# F103ZET6.net
KiCad netlist of a schematic drawn in Altium Designer
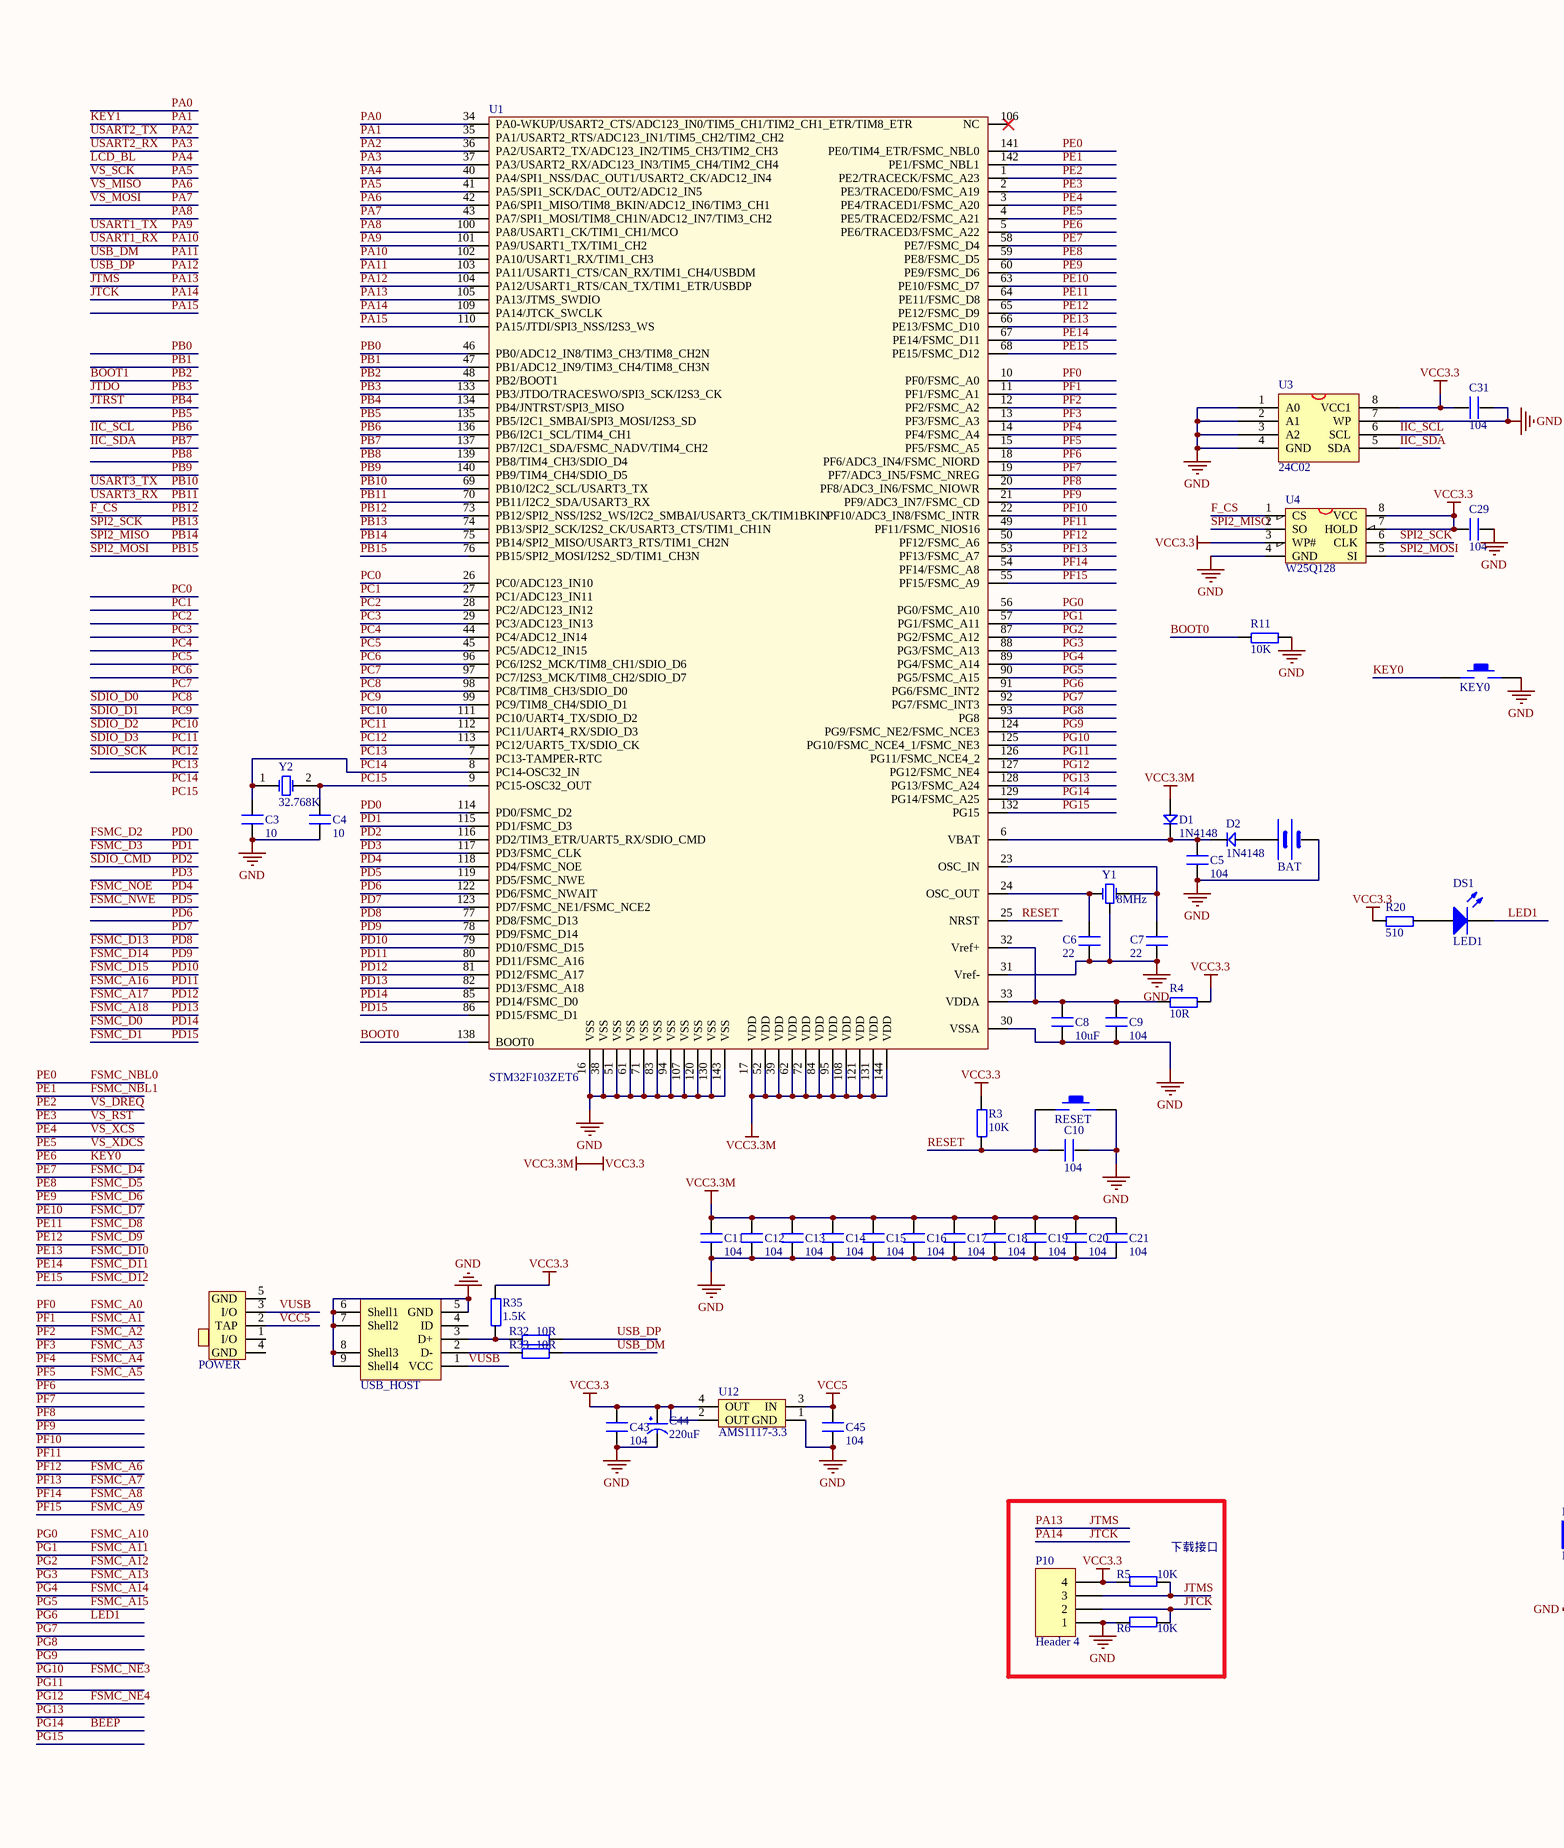
[diagram p0: F103ZET6.SchDoc, left]
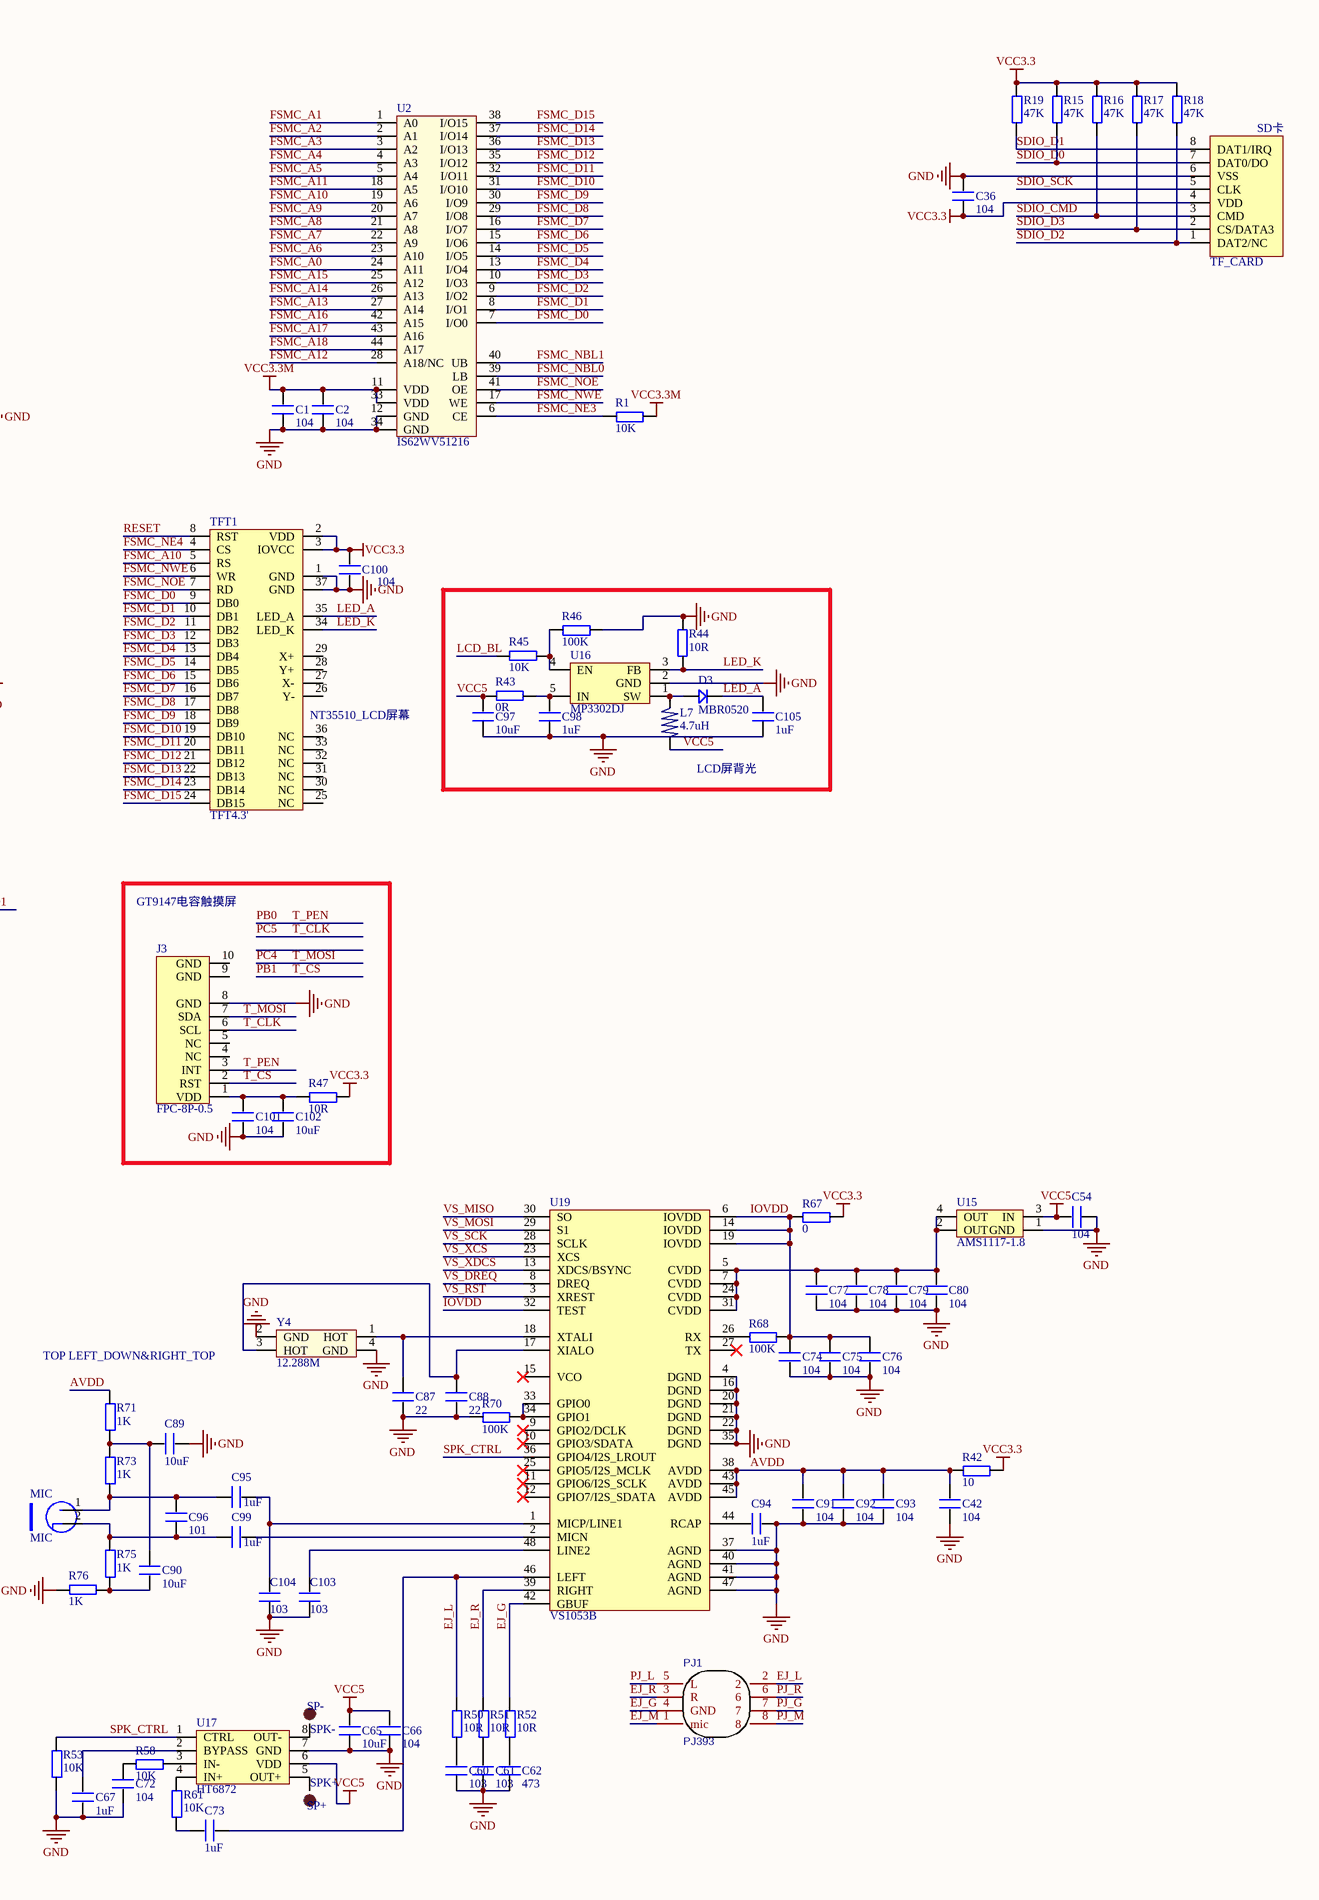
[diagram p1: F103ZET6.SchDoc, right]

(export (version "E")
  (design (tool "Eeschema 10.0.6"))
  (components
    (comp (ref "BAT")
      (value "BATT")
      (footprint "CR1220_A")
      (libsource (lib "WarShip V3 STM32103封装库") (part "BAT"))
    )
    (comp (ref "C1")
      (value "104")
      (footprint "C 0603_M")
      (libsource (lib "WarShip V3 STM32103封装库") (part "C"))
    )
    (comp (ref "C2")
      (value "104")
      (footprint "C 0603_M")
      (libsource (lib "WarShip V3 STM32103封装库") (part "C"))
    )
    (comp (ref "C3")
      (value "10")
      (footprint "C 0603_M")
      (libsource (lib "WarShip V3 STM32103封装库") (part "C"))
    )
    (comp (ref "C4")
      (value "10")
      (footprint "C 0603_M")
      (libsource (lib "WarShip V3 STM32103封装库") (part "C"))
    )
    (comp (ref "C5")
      (value "104")
      (footprint "C 0603_M")
      (libsource (lib "WarShip V3 STM32103封装库") (part "C"))
    )
    (comp (ref "C6")
      (value "22")
      (footprint "C 0603_M")
      (libsource (lib "WarShip V3 STM32103封装库") (part "C"))
    )
    (comp (ref "C7")
      (value "22")
      (footprint "C 0603_M")
      (libsource (lib "WarShip V3 STM32103封装库") (part "C"))
    )
    (comp (ref "C8")
      (value "10uF")
      (footprint "C 0805_M")
      (libsource (lib "WarShip V3 STM32103封装库") (part "C"))
    )
    (comp (ref "C9")
      (value "104")
      (footprint "C 0603_M")
      (libsource (lib "WarShip V3 STM32103封装库") (part "C"))
    )
    (comp (ref "C10")
      (value "104")
      (footprint "C 0603_M")
      (libsource (lib "WarShip V3 STM32103封装库") (part "C"))
    )
    (comp (ref "C11")
      (value "104")
      (footprint "C 0603_M")
      (libsource (lib "WarShip V3 STM32103封装库") (part "C"))
    )
    (comp (ref "C12")
      (value "104")
      (footprint "C 0603_M")
      (libsource (lib "WarShip V3 STM32103封装库") (part "C"))
    )
    (comp (ref "C13")
      (value "104")
      (footprint "C 0603_M")
      (libsource (lib "WarShip V3 STM32103封装库") (part "C"))
    )
    (comp (ref "C14")
      (value "104")
      (footprint "C 0603_M")
      (libsource (lib "WarShip V3 STM32103封装库") (part "C"))
    )
    (comp (ref "C15")
      (value "104")
      (footprint "C 0603_M")
      (libsource (lib "WarShip V3 STM32103封装库") (part "C"))
    )
    (comp (ref "C16")
      (value "104")
      (footprint "C 0603_M")
      (libsource (lib "WarShip V3 STM32103封装库") (part "C"))
    )
    (comp (ref "C17")
      (value "104")
      (footprint "C 0603_M")
      (libsource (lib "WarShip V3 STM32103封装库") (part "C"))
    )
    (comp (ref "C18")
      (value "104")
      (footprint "C 0603_M")
      (libsource (lib "WarShip V3 STM32103封装库") (part "C"))
    )
    (comp (ref "C19")
      (value "104")
      (footprint "C 0603_M")
      (libsource (lib "WarShip V3 STM32103封装库") (part "C"))
    )
    (comp (ref "C20")
      (value "104")
      (footprint "C 0603_M")
      (libsource (lib "WarShip V3 STM32103封装库") (part "C"))
    )
    (comp (ref "C21")
      (value "104")
      (footprint "C 0603_M")
      (libsource (lib "WarShip V3 STM32103封装库") (part "C"))
    )
    (comp (ref "C29")
      (value "104")
      (footprint "C 0603_M")
      (libsource (lib "WarShip V3 STM32103封装库") (part "C"))
    )
    (comp (ref "C31")
      (value "104")
      (footprint "C 0603_M")
      (libsource (lib "WarShip V3 STM32103封装库") (part "C"))
    )
    (comp (ref "C36")
      (value "104")
      (footprint "C 0603_M")
      (libsource (lib "WarShip V3 STM32103封装库") (part "C"))
    )
    (comp (ref "C42") (value "104") (footprint "C 0603_M") (libsource (lib "ATK-VS1053 MP3") (part "C")))
    (comp (ref "C43")
      (value "104")
      (footprint "C 0603_M")
      (libsource (lib "WarShip V3 STM32103封装库") (part "C"))
    )
    (comp (ref "C44")
      (value "220uF")
      (footprint "CT 6*6 - C")
      (libsource (lib "WarShip V3 STM32103封装库") (part "CAP"))
    )
    (comp (ref "C45")
      (value "104")
      (footprint "C 0603_M")
      (libsource (lib "WarShip V3 STM32103封装库") (part "C"))
    )
    (comp (ref "C54") (value "104") (footprint "C 0603_M") (libsource (lib "ATK-VS1053 MP3") (part "C")))
    (comp (ref "C60")
      (value "103")
      (footprint "C 0603_M")
      (libsource (lib "WarShip V3 STM32103封装库") (part "C"))
    )
    (comp (ref "C61")
      (value "103")
      (footprint "C 0603_M")
      (libsource (lib "WarShip V3 STM32103封装库") (part "C"))
    )
    (comp (ref "C62")
      (value "473")
      (footprint "C 0603_M")
      (libsource (lib "WarShip V3 STM32103封装库") (part "C"))
    )
    (comp (ref "C65")
      (value "10uF")
      (footprint "C 0805_M")
      (libsource (lib "WarShip V3 STM32103封装库") (part "C"))
    )
    (comp (ref "C66")
      (value "104")
      (footprint "C 0603_M")
      (libsource (lib "WarShip V3 STM32103封装库") (part "C"))
    )
    (comp (ref "C67")
      (value "1uF")
      (footprint "C 0603_M")
      (libsource (lib "WarShip V3 STM32103封装库") (part "C"))
    )
    (comp (ref "C72")
      (value "104")
      (footprint "C 0603_M")
      (libsource (lib "WarShip V3 STM32103封装库") (part "C"))
    )
    (comp (ref "C73")
      (value "1uF")
      (footprint "C 0603_M")
      (libsource (lib "WarShip V3 STM32103封装库") (part "C"))
    )
    (comp (ref "C74") (value "104") (footprint "C 0603_M") (libsource (lib "ATK-VS1053 MP3") (part "C")))
    (comp (ref "C75") (value "104") (footprint "C 0603_M") (libsource (lib "ATK-VS1053 MP3") (part "C")))
    (comp (ref "C76") (value "104") (footprint "C 0603_M") (libsource (lib "ATK-VS1053 MP3") (part "C")))
    (comp (ref "C77") (value "104") (footprint "C 0603_M") (libsource (lib "ATK-VS1053 MP3") (part "C")))
    (comp (ref "C78") (value "104") (footprint "C 0603_M") (libsource (lib "ATK-VS1053 MP3") (part "C")))
    (comp (ref "C79") (value "104") (footprint "C 0603_M") (libsource (lib "ATK-VS1053 MP3") (part "C")))
    (comp (ref "C80") (value "104") (footprint "C 0603_M") (libsource (lib "ATK-VS1053 MP3") (part "C")))
    (comp (ref "C87") (value "22") (footprint "C 0603_M") (libsource (lib "ATK-VS1053 MP3") (part "C")))
    (comp (ref "C88") (value "22") (footprint "C 0603_M") (libsource (lib "ATK-VS1053 MP3") (part "C")))
    (comp (ref "C89")
      (value "10uF")
      (footprint "C 0805_M")
      (libsource (lib "WarShip V3 STM32103封装库") (part "C"))
    )
    (comp (ref "C90")
      (value "10uF")
      (footprint "C 0805_M")
      (libsource (lib "WarShip V3 STM32103封装库") (part "C"))
    )
    (comp (ref "C91") (value "104") (footprint "C 0603_M") (libsource (lib "ATK-VS1053 MP3") (part "C")))
    (comp (ref "C92") (value "104") (footprint "C 0603_M") (libsource (lib "ATK-VS1053 MP3") (part "C")))
    (comp (ref "C93") (value "104") (footprint "C 0603_M") (libsource (lib "ATK-VS1053 MP3") (part "C")))
    (comp (ref "C94") (value "1uF") (footprint "C 0603_M") (libsource (lib "ATK-VS1053 MP3") (part "C")))
    (comp (ref "C95")
      (value "1uF")
      (footprint "C 0603_M")
      (libsource (lib "WarShip V3 STM32103封装库") (part "C"))
    )
    (comp (ref "C96")
      (value "101")
      (footprint "C 0603_M")
      (libsource (lib "WarShip V3 STM32103封装库") (part "C"))
    )
    (comp (ref "C97") (value "10uF") (footprint "C 0603_M") (libsource (lib "阿波罗STM32F4&F7底板封装库") (part "C")))
    (comp (ref "C98") (value "1uF") (footprint "C 0603_M") (libsource (lib "阿波罗STM32F4&F7底板封装库") (part "C")))
    (comp (ref "C99")
      (value "1uF")
      (footprint "C 0603_M")
      (libsource (lib "WarShip V3 STM32103封装库") (part "C"))
    )
    (comp (ref "C100") (value "104") (footprint "C 0603_M") (libsource (lib "阿波罗STM32F4&F7底板封装库") (part "C")))
    (comp (ref "C101") (value "104") (footprint "C 0603_M") (libsource (lib "阿波罗STM32F4&F7底板封装库") (part "C")))
    (comp (ref "C102")
      (value "10uF")
      (footprint "C 0603_M")
      (libsource (lib "阿波罗STM32F4&F7底板封装库") (part "C"))
    )
    (comp (ref "C103")
      (value "103")
      (footprint "C 0603_M")
      (libsource (lib "WarShip V3 STM32103封装库") (part "C"))
    )
    (comp (ref "C104")
      (value "103")
      (footprint "C 0603_M")
      (libsource (lib "WarShip V3 STM32103封装库") (part "C"))
    )
    (comp (ref "C105") (value "1uF") (footprint "C 0603_M") (libsource (lib "阿波罗STM32F4&F7底板封装库") (part "C")))
    (comp (ref "D1")
      (value "1N4148")
      (footprint "DIODE_SOP")
      (libsource (lib "WarShip V3 STM32103封装库") (part "D"))
    )
    (comp (ref "D2")
      (value "1N4148")
      (footprint "DIODE_SOP")
      (libsource (lib "WarShip V3 STM32103封装库") (part "D"))
    )
    (comp (ref "D3")
      (value "MBR0520")
      (footprint "SOD-123")
      (description "1N4148")
      (libsource (lib "ATK-4.3' TFTLCD电容触摸屏模块_V1.2") (part "D"))
    )
    (comp (ref "DS1")
      (value "LED1")
      (footprint "LED 0603R")
      (description "Typical RED, GREEN, YELLOW, AMBER GaAs LED")
      (fields (field (name "PUBLISHER") "Altium Limited"))
      (libsource (lib "WarShip V3 STM32103封装库") (part "LED2"))
    )
    (comp (ref "J3")
      (value "FPC-8P-0.5")
      (footprint "FPC-8P")
      (description "FPC-8P-0.5mm")
      (libsource (lib "ATK-4.3' TFTLCD电容触摸屏模块_V1.2") (part "FPC-8"))
    )
    (comp (ref "KEY0")
      (value "KEY_M")
      (footprint "TSW SMD-3*6*2.5")
      (libsource (lib "WarShip V3 STM32103封装库") (part "KEY_M"))
    )
    (comp (ref "L7")
      (value "4.7uH")
      (footprint "L_SOP4")
      (libsource (lib "ATK-4.3' TFTLCD电容触摸屏模块_V1.2") (part "L"))
    )
    (comp (ref "MIC") (value "MIC") (footprint "MIC-6022") (libsource (lib "ATK-VS1053 MP3") (part "MIC")))
    (comp (ref "P10")
      (value "Header 4")
      (footprint "HDR2.54-LI-4P")
      (description "Header, 4-Pin")
      (fields (field (name "PUBLISHER") "Altium Limited"))
      (libsource (lib "WarShip V3 STM32103封装库") (part "Header 4"))
    )
    (comp (ref "PJ1")
      (value "PJ393")
      (footprint "PJ393")
      (fields
        (field (name "BOM_MANUFACTURER PART") "?")
        (field (name "CONTRIBUTOR") "infinite_possibilities")
      )
      (libsource (lib "PJ393") (part "PJ393"))
    )
    (comp (ref "POWER")
      (value "BUTTON_DIP3")
      (footprint "MSK-12C01-07")
      (description "拨动开关SS-12F44")
      (libsource (lib "Pandora_STM32L4_Board_V2.4") (part "BUTTON_DIP3"))
    )
    (comp (ref "R1")
      (value "10K")
      (footprint "R 0603_M")
      (libsource (lib "WarShip V3 STM32103封装库") (part "R"))
    )
    (comp (ref "R3")
      (value "10K")
      (footprint "R 0603_M")
      (libsource (lib "WarShip V3 STM32103封装库") (part "R"))
    )
    (comp (ref "R4")
      (value "10R")
      (footprint "R 0603_M")
      (libsource (lib "WarShip V3 STM32103封装库") (part "R"))
    )
    (comp (ref "R5")
      (value "10K")
      (footprint "R 0603_M")
      (libsource (lib "WarShip V3 STM32103封装库") (part "R"))
    )
    (comp (ref "R6")
      (value "10K")
      (footprint "R 0603_M")
      (libsource (lib "WarShip V3 STM32103封装库") (part "R"))
    )
    (comp (ref "R11")
      (value "10K")
      (footprint "R 0603_M")
      (libsource (lib "WarShip V3 STM32103封装库") (part "R"))
    )
    (comp (ref "R15")
      (value "47K")
      (footprint "R 0603_M")
      (libsource (lib "WarShip V3 STM32103封装库") (part "R"))
    )
    (comp (ref "R16")
      (value "47K")
      (footprint "R 0603_M")
      (libsource (lib "WarShip V3 STM32103封装库") (part "R"))
    )
    (comp (ref "R17")
      (value "47K")
      (footprint "R 0603_M")
      (libsource (lib "WarShip V3 STM32103封装库") (part "R"))
    )
    (comp (ref "R18")
      (value "47K")
      (footprint "R 0603_M")
      (libsource (lib "WarShip V3 STM32103封装库") (part "R"))
    )
    (comp (ref "R19")
      (value "47K")
      (footprint "R 0603_M")
      (libsource (lib "WarShip V3 STM32103封装库") (part "R"))
    )
    (comp (ref "R20")
      (value "510")
      (footprint "R 0603_M")
      (libsource (lib "WarShip V3 STM32103封装库") (part "R"))
    )
    (comp (ref "R32")
      (value "10R")
      (footprint "R 0603_M")
      (libsource (lib "WarShip V3 STM32103封装库") (part "R"))
    )
    (comp (ref "R33")
      (value "10R")
      (footprint "R 0603_M")
      (libsource (lib "WarShip V3 STM32103封装库") (part "R"))
    )
    (comp (ref "R35")
      (value "1.5K")
      (footprint "R 0603_M")
      (libsource (lib "WarShip V3 STM32103封装库") (part "R"))
    )
    (comp (ref "R42") (value "10") (footprint "R 0603_M") (libsource (lib "ATK-VS1053 MP3") (part "R")))
    (comp (ref "R43") (value "0R") (footprint "R 0603_M") (libsource (lib "阿波罗STM32F4&F7底板封装库") (part "R")))
    (comp (ref "R44") (value "10R") (footprint "R 0603_M") (libsource (lib "阿波罗STM32F4&F7底板封装库") (part "R")))
    (comp (ref "R45") (value "10K") (footprint "R 0603_M") (libsource (lib "阿波罗STM32F4&F7底板封装库") (part "R")))
    (comp (ref "R46") (value "100K") (footprint "R 0603_M") (libsource (lib "阿波罗STM32F4&F7底板封装库") (part "R")))
    (comp (ref "R47") (value "10R") (footprint "R 0603_M") (libsource (lib "阿波罗STM32F4&F7底板封装库") (part "R")))
    (comp (ref "R50")
      (value "10R")
      (footprint "R 0603_M")
      (libsource (lib "WarShip V3 STM32103封装库") (part "R"))
    )
    (comp (ref "R51")
      (value "10R")
      (footprint "R 0603_M")
      (libsource (lib "WarShip V3 STM32103封装库") (part "R"))
    )
    (comp (ref "R52")
      (value "10R")
      (footprint "R 0603_M")
      (libsource (lib "WarShip V3 STM32103封装库") (part "R"))
    )
    (comp (ref "R53")
      (value "10K")
      (footprint "R 0603_M")
      (libsource (lib "WarShip V3 STM32103封装库") (part "R"))
    )
    (comp (ref "R58")
      (value "10K")
      (footprint "R 0603_M")
      (libsource (lib "WarShip V3 STM32103封装库") (part "R"))
    )
    (comp (ref "R61")
      (value "10K")
      (footprint "R 0603_M")
      (libsource (lib "WarShip V3 STM32103封装库") (part "R"))
    )
    (comp (ref "R67") (value "0") (footprint "R 0603_M") (libsource (lib "ATK-VS1053 MP3") (part "R")))
    (comp (ref "R68") (value "100K") (footprint "R 0603_M") (libsource (lib "ATK-VS1053 MP3") (part "R")))
    (comp (ref "R70") (value "100K") (footprint "R 0603_M") (libsource (lib "ATK-VS1053 MP3") (part "R")))
    (comp (ref "R71")
      (value "1K")
      (footprint "R 0603_M")
      (libsource (lib "WarShip V3 STM32103封装库") (part "R"))
    )
    (comp (ref "R73")
      (value "1K")
      (footprint "R 0603_M")
      (libsource (lib "WarShip V3 STM32103封装库") (part "R"))
    )
    (comp (ref "R75")
      (value "1K")
      (footprint "R 0603_M")
      (libsource (lib "WarShip V3 STM32103封装库") (part "R"))
    )
    (comp (ref "R76")
      (value "1K")
      (footprint "R 0603_M")
      (libsource (lib "WarShip V3 STM32103封装库") (part "R"))
    )
    (comp (ref "RESET")
      (value "KEY_M")
      (footprint "TSW SMD-3*6*2.5")
      (libsource (lib "WarShip V3 STM32103封装库") (part "KEY_M"))
    )
    (comp (ref "SP+")
      (value "SPK+")
      (footprint "TP-1.5")
      (description "测试点")
      (libsource (lib "WarShip V3 STM32103封装库") (part "TEST-POINT"))
    )
    (comp (ref "SP-")
      (value "SPK-")
      (footprint "TP-1.5")
      (description "测试点")
      (libsource (lib "WarShip V3 STM32103封装库") (part "TEST-POINT"))
    )
    (comp (ref "TFT1")
      (value "TFT4.3'")
      (footprint "TFT4.3'")
      (description "4.3寸,电容/电阻触摸,分辨率:480*800")
      (libsource (lib "ATK-4.3' TFTLCD电容触摸屏模块_V1.2") (part "TFT4.3‘"))
    )
    (comp (ref "TF_CARD")
      (value "SD-MICRO-TF")
      (footprint "SD-MICRO-TF")
      (description "SD,MICRO,TF")
      (libsource (lib "Pandora_STM32L4_Board_V2.4") (part "SD-MICRO-TF"))
    )
    (comp (ref "U1")
      (value "STM32F103ZET6")
      (footprint "LQFP144")
      (libsource (lib "WarShip V3 STM32103封装库") (part "STM32F103ZET6"))
    )
    (comp (ref "U2")
      (value "IS62WV51216")
      (footprint "TSOP44")
      (libsource (lib "WarShip V3 STM32103封装库") (part "IS61LV51216"))
    )
    (comp (ref "U3")
      (value "24C02")
      (footprint "SOP-8")
      (libsource (lib "WarShip V3 STM32103封装库") (part "24C256"))
    )
    (comp (ref "U4")
      (value "W25Q128")
      (footprint "SOIC-8")
      (description "W25X16;SST25VF016;MX25L1605")
      (libsource (lib "WarShip V3 STM32103封装库") (part "W25X16"))
    )
    (comp (ref "U12")
      (value "AMS1117-3.3")
      (footprint "AMS1117")
      (libsource (lib "WarShip V3 STM32103封装库") (part "AMS1117"))
    )
    (comp (ref "U15")
      (value "AMS1117-1.8")
      (footprint "AMS1117")
      (libsource (lib "ATK-VS1053 MP3") (part "AMS1117"))
    )
    (comp (ref "U16")
      (value "MP3302DJ")
      (footprint "SOT-23-5")
      (description "LCD背光IC")
      (libsource (lib "ATK-4.3' TFTLCD电容触摸屏模块_V1.2") (part "MP3302"))
    )
    (comp (ref "U17")
      (value "HT6872")
      (footprint "SOP-8")
      (description "HT6871")
      (libsource (lib "WarShip V3 STM32103封装库") (part "HT6871"))
    )
    (comp (ref "U19")
      (value "VS1053B")
      (footprint "mTQFP48")
      (libsource (lib "ATK-VS1053 MP3") (part "VS1053"))
    )
    (comp (ref "USB_HOST")
      (value "J-MICRO-USB-5S")
      (footprint "USB-AB-5S")
      (description "Micro USB 5.9有柱脚长1.25加长针")
      (libsource (lib "Pandora_STM32L4_Board_V2.4") (part "J-MICRO-USB-5S"))
    )
    (comp (ref "Y1")
      (value "8MHz")
      (footprint "Y-XTAL-3215-3P")
      (description "XTAL,3215,8MHz")
      (libsource (lib "Pandora_STM32L4_Board_V2.4") (part "Y-3215-8M"))
    )
    (comp (ref "Y2")
      (value "32.768K")
      (footprint "Y-XTAL-3215-2P")
      (description "Crystal Oscillator")
      (fields (field (name "PUBLISHER") "Altium Limited"))
      (libsource (lib "WarShip V3 STM32103封装库") (part "XTAL"))
    )
    (comp (ref "Y4")
      (value "12.288M")
      (footprint "OSC 3225-4P")
      (description "3225贴片无源晶振")
      (libsource (lib "STM32F767核心板封装库") (part "XTAL_3225"))
    )
  )
  (nets
    (net (code "1") (name "/AVDD") (class "Default")
      (node (ref "C42") (pin "2") (pintype "passive"))
      (node (ref "C91") (pin "2") (pintype "passive"))
      (node (ref "C92") (pin "2") (pintype "passive"))
      (node (ref "C93") (pin "2") (pintype "passive"))
      (node (ref "R42") (pin "1") (pintype "passive"))
      (node (ref "R71") (pin "2") (pintype "passive"))
      (node (ref "U19") (pin "38") (pinfunction "AVDD_38") (pintype "passive"))
      (node (ref "U19") (pin "43") (pinfunction "AVDD_43") (pintype "passive"))
      (node (ref "U19") (pin "45") (pinfunction "AVDD_45") (pintype "passive"))
    )
    (net (code "2") (name "/BEEP") (class "Default")
      (node (ref "U1") (pin "129") (pinfunction "PG14/FSMC_A25_129") (pintype "passive"))
    )
    (net (code "3") (name "/BOOT0") (class "Default")
      (node (ref "R11") (pin "1") (pintype "passive"))
      (node (ref "U1") (pin "138") (pinfunction "BOOT0_138") (pintype "passive"))
    )
    (net (code "4") (name "/BOOT1") (class "Default")
      (node (ref "U1") (pin "48") (pinfunction "PB2/BOOT1_48") (pintype "passive"))
    )
    (net (code "5") (name "/EJ_G") (class "Default")
      (node (ref "PJ1") (pin "4") (pinfunction "GND_4") (pintype "passive"))
      (node (ref "R52") (pin "2") (pintype "passive"))
      (node (ref "U19") (pin "42") (pinfunction "GBUF_42") (pintype "passive"))
    )
    (net (code "6") (name "/EJ_L") (class "Default")
      (node (ref "C73") (pin "1") (pintype "passive"))
      (node (ref "PJ1") (pin "2") (pinfunction "2_2") (pintype "passive"))
      (node (ref "R50") (pin "2") (pintype "passive"))
      (node (ref "U19") (pin "46") (pinfunction "LEFT_46") (pintype "passive"))
    )
    (net (code "7") (name "/EJ_M") (class "Default")
      (node (ref "PJ1") (pin "1") (pinfunction "mic_1") (pintype "passive"))
    )
    (net (code "8") (name "/EJ_R") (class "Default")
      (node (ref "PJ1") (pin "3") (pinfunction "R_3") (pintype "passive"))
      (node (ref "R51") (pin "2") (pintype "passive"))
      (node (ref "U19") (pin "39") (pinfunction "RIGHT_39") (pintype "passive"))
    )
    (net (code "9") (name "/FSMC_A0") (class "Default")
      (node (ref "U1") (pin "10") (pinfunction "PF0/FSMC_A0_10") (pintype "passive"))
      (node (ref "U2") (pin "24") (pinfunction "A11_24") (pintype "passive"))
    )
    (net (code "10") (name "/FSMC_A1") (class "Default")
      (node (ref "U1") (pin "11") (pinfunction "PF1/FSMC_A1_11") (pintype "passive"))
      (node (ref "U2") (pin "1") (pinfunction "A0_1") (pintype "passive"))
    )
    (net (code "11") (name "/FSMC_A2") (class "Default")
      (node (ref "U1") (pin "12") (pinfunction "PF2/FSMC_A2_12") (pintype "passive"))
      (node (ref "U2") (pin "2") (pinfunction "A1_2") (pintype "passive"))
    )
    (net (code "12") (name "/FSMC_A3") (class "Default")
      (node (ref "U1") (pin "13") (pinfunction "PF3/FSMC_A3_13") (pintype "passive"))
      (node (ref "U2") (pin "3") (pinfunction "A2_3") (pintype "passive"))
    )
    (net (code "13") (name "/FSMC_A4") (class "Default")
      (node (ref "U1") (pin "14") (pinfunction "PF4/FSMC_A4_14") (pintype "passive"))
      (node (ref "U2") (pin "4") (pinfunction "A3_4") (pintype "passive"))
    )
    (net (code "14") (name "/FSMC_A5") (class "Default")
      (node (ref "U1") (pin "15") (pinfunction "PF5/FSMC_A5_15") (pintype "passive"))
      (node (ref "U2") (pin "5") (pinfunction "A4_5") (pintype "passive"))
    )
    (net (code "15") (name "/FSMC_A6") (class "Default")
      (node (ref "U1") (pin "50") (pinfunction "PF12/FSMC_A6_50") (pintype "passive"))
      (node (ref "U2") (pin "23") (pinfunction "A10_23") (pintype "passive"))
    )
    (net (code "16") (name "/FSMC_A7") (class "Default")
      (node (ref "U1") (pin "53") (pinfunction "PF13/FSMC_A7_53") (pintype "passive"))
      (node (ref "U2") (pin "22") (pinfunction "A9_22") (pintype "passive"))
    )
    (net (code "17") (name "/FSMC_A8") (class "Default")
      (node (ref "U1") (pin "54") (pinfunction "PF14/FSMC_A8_54") (pintype "passive"))
      (node (ref "U2") (pin "21") (pinfunction "A8_21") (pintype "passive"))
    )
    (net (code "18") (name "/FSMC_A9") (class "Default")
      (node (ref "U1") (pin "55") (pinfunction "PF15/FSMC_A9_55") (pintype "passive"))
      (node (ref "U2") (pin "20") (pinfunction "A7_20") (pintype "passive"))
    )
    (net (code "19") (name "/FSMC_A10") (class "Default")
      (node (ref "TFT1") (pin "5") (pinfunction "RS_5") (pintype "passive"))
      (node (ref "U1") (pin "56") (pinfunction "PG0/FSMC_A10_56") (pintype "passive"))
      (node (ref "U2") (pin "19") (pinfunction "A6_19") (pintype "passive"))
    )
    (net (code "20") (name "/FSMC_A11") (class "Default")
      (node (ref "U1") (pin "57") (pinfunction "PG1/FSMC_A11_57") (pintype "passive"))
      (node (ref "U2") (pin "18") (pinfunction "A5_18") (pintype "passive"))
    )
    (net (code "21") (name "/FSMC_A12") (class "Default")
      (node (ref "U1") (pin "87") (pinfunction "PG2/FSMC_A12_87") (pintype "passive"))
      (node (ref "U2") (pin "28") (pinfunction "A18/NC_28") (pintype "passive"))
    )
    (net (code "22") (name "/FSMC_A13") (class "Default")
      (node (ref "U1") (pin "88") (pinfunction "PG3/FSMC_A13_88") (pintype "passive"))
      (node (ref "U2") (pin "27") (pinfunction "A14_27") (pintype "passive"))
    )
    (net (code "23") (name "/FSMC_A14") (class "Default")
      (node (ref "U1") (pin "89") (pinfunction "PG4/FSMC_A14_89") (pintype "passive"))
      (node (ref "U2") (pin "26") (pinfunction "A13_26") (pintype "passive"))
    )
    (net (code "24") (name "/FSMC_A15") (class "Default")
      (node (ref "U1") (pin "90") (pinfunction "PG5/FSMC_A15_90") (pintype "passive"))
      (node (ref "U2") (pin "25") (pinfunction "A12_25") (pintype "passive"))
    )
    (net (code "25") (name "/FSMC_A16") (class "Default")
      (node (ref "U1") (pin "80") (pinfunction "PD11/FSMC_A16_80") (pintype "passive"))
      (node (ref "U2") (pin "42") (pinfunction "A15_42") (pintype "passive"))
    )
    (net (code "26") (name "/FSMC_A17") (class "Default")
      (node (ref "U1") (pin "81") (pinfunction "PD12/FSMC_A17_81") (pintype "passive"))
      (node (ref "U2") (pin "43") (pinfunction "A16_43") (pintype "passive"))
    )
    (net (code "27") (name "/FSMC_A18") (class "Default")
      (node (ref "U1") (pin "82") (pinfunction "PD13/FSMC_A18_82") (pintype "passive"))
      (node (ref "U2") (pin "44") (pinfunction "A17_44") (pintype "passive"))
    )
    (net (code "28") (name "/FSMC_D0") (class "Default")
      (node (ref "TFT1") (pin "9") (pinfunction "DB0_9") (pintype "passive"))
      (node (ref "U1") (pin "85") (pinfunction "PD14/FSMC_D0_85") (pintype "passive"))
      (node (ref "U2") (pin "7") (pinfunction "I/O0_7") (pintype "passive"))
    )
    (net (code "29") (name "/FSMC_D1") (class "Default")
      (node (ref "TFT1") (pin "10") (pinfunction "DB1_10") (pintype "passive"))
      (node (ref "U1") (pin "86") (pinfunction "PD15/FSMC_D1_86") (pintype "passive"))
      (node (ref "U2") (pin "8") (pinfunction "I/O1_8") (pintype "passive"))
    )
    (net (code "30") (name "/FSMC_D2") (class "Default")
      (node (ref "TFT1") (pin "11") (pinfunction "DB2_11") (pintype "passive"))
      (node (ref "U1") (pin "114") (pinfunction "PD0/FSMC_D2_114") (pintype "passive"))
      (node (ref "U2") (pin "9") (pinfunction "I/O2_9") (pintype "passive"))
    )
    (net (code "31") (name "/FSMC_D3") (class "Default")
      (node (ref "TFT1") (pin "12") (pinfunction "DB3_12") (pintype "passive"))
      (node (ref "U1") (pin "115") (pinfunction "PD1/FSMC_D3_115") (pintype "passive"))
      (node (ref "U2") (pin "10") (pinfunction "I/O3_10") (pintype "passive"))
    )
    (net (code "32") (name "/FSMC_D4") (class "Default")
      (node (ref "TFT1") (pin "13") (pinfunction "DB4_13") (pintype "passive"))
      (node (ref "U1") (pin "58") (pinfunction "PE7/FSMC_D4_58") (pintype "passive"))
      (node (ref "U2") (pin "13") (pinfunction "I/O4_13") (pintype "passive"))
    )
    (net (code "33") (name "/FSMC_D5") (class "Default")
      (node (ref "TFT1") (pin "14") (pinfunction "DB5_14") (pintype "passive"))
      (node (ref "U1") (pin "59") (pinfunction "PE8/FSMC_D5_59") (pintype "passive"))
      (node (ref "U2") (pin "14") (pinfunction "I/O5_14") (pintype "passive"))
    )
    (net (code "34") (name "/FSMC_D6") (class "Default")
      (node (ref "TFT1") (pin "15") (pinfunction "DB6_15") (pintype "passive"))
      (node (ref "U1") (pin "60") (pinfunction "PE9/FSMC_D6_60") (pintype "passive"))
      (node (ref "U2") (pin "15") (pinfunction "I/O6_15") (pintype "passive"))
    )
    (net (code "35") (name "/FSMC_D7") (class "Default")
      (node (ref "TFT1") (pin "16") (pinfunction "DB7_16") (pintype "passive"))
      (node (ref "U1") (pin "63") (pinfunction "PE10/FSMC_D7_63") (pintype "passive"))
      (node (ref "U2") (pin "16") (pinfunction "I/O7_16") (pintype "passive"))
    )
    (net (code "36") (name "/FSMC_D8") (class "Default")
      (node (ref "TFT1") (pin "17") (pinfunction "DB8_17") (pintype "passive"))
      (node (ref "U1") (pin "64") (pinfunction "PE11/FSMC_D8_64") (pintype "passive"))
      (node (ref "U2") (pin "29") (pinfunction "I/O8_29") (pintype "passive"))
    )
    (net (code "37") (name "/FSMC_D9") (class "Default")
      (node (ref "TFT1") (pin "18") (pinfunction "DB9_18") (pintype "passive"))
      (node (ref "U1") (pin "65") (pinfunction "PE12/FSMC_D9_65") (pintype "passive"))
      (node (ref "U2") (pin "30") (pinfunction "I/O9_30") (pintype "passive"))
    )
    (net (code "38") (name "/FSMC_D10") (class "Default")
      (node (ref "TFT1") (pin "19") (pinfunction "DB10_19") (pintype "passive"))
      (node (ref "U1") (pin "66") (pinfunction "PE13/FSMC_D10_66") (pintype "passive"))
      (node (ref "U2") (pin "31") (pinfunction "I/O10_31") (pintype "passive"))
    )
    (net (code "39") (name "/FSMC_D11") (class "Default")
      (node (ref "TFT1") (pin "20") (pinfunction "DB11_20") (pintype "passive"))
      (node (ref "U1") (pin "67") (pinfunction "PE14/FSMC_D11_67") (pintype "passive"))
      (node (ref "U2") (pin "32") (pinfunction "I/O11_32") (pintype "passive"))
    )
    (net (code "40") (name "/FSMC_D12") (class "Default")
      (node (ref "TFT1") (pin "21") (pinfunction "DB12_21") (pintype "passive"))
      (node (ref "U1") (pin "68") (pinfunction "PE15/FSMC_D12_68") (pintype "passive"))
      (node (ref "U2") (pin "35") (pinfunction "I/O12_35") (pintype "passive"))
    )
    (net (code "41") (name "/FSMC_D13") (class "Default")
      (node (ref "TFT1") (pin "22") (pinfunction "DB13_22") (pintype "passive"))
      (node (ref "U1") (pin "77") (pinfunction "PD8/FSMC_D13_77") (pintype "passive"))
      (node (ref "U2") (pin "36") (pinfunction "I/O13_36") (pintype "passive"))
    )
    (net (code "42") (name "/FSMC_D14") (class "Default")
      (node (ref "TFT1") (pin "23") (pinfunction "DB14_23") (pintype "passive"))
      (node (ref "U1") (pin "78") (pinfunction "PD9/FSMC_D14_78") (pintype "passive"))
      (node (ref "U2") (pin "37") (pinfunction "I/O14_37") (pintype "passive"))
    )
    (net (code "43") (name "/FSMC_D15") (class "Default")
      (node (ref "TFT1") (pin "24") (pinfunction "DB15_24") (pintype "passive"))
      (node (ref "U1") (pin "79") (pinfunction "PD10/FSMC_D15_79") (pintype "passive"))
      (node (ref "U2") (pin "38") (pinfunction "I/O15_38") (pintype "passive"))
    )
    (net (code "44") (name "/FSMC_NBL0") (class "Default")
      (node (ref "U1") (pin "141") (pinfunction "PE0/TIM4_ETR/FSMC_NBL0_141") (pintype "passive"))
      (node (ref "U2") (pin "39") (pinfunction "LB_39") (pintype "passive"))
    )
    (net (code "45") (name "/FSMC_NBL1") (class "Default")
      (node (ref "U1") (pin "142") (pinfunction "PE1/FSMC_NBL1_142") (pintype "passive"))
      (node (ref "U2") (pin "40") (pinfunction "UB_40") (pintype "passive"))
    )
    (net (code "46") (name "/FSMC_NE3") (class "Default")
      (node (ref "R1") (pin "1") (pintype "passive"))
      (node (ref "U1") (pin "125") (pinfunction "PG10/FSMC_NCE4_1/FSMC_NE3_125") (pintype "passive"))
      (node (ref "U2") (pin "6") (pinfunction "CE_6") (pintype "passive"))
    )
    (net (code "47") (name "/FSMC_NE4") (class "Default")
      (node (ref "TFT1") (pin "4") (pinfunction "CS_4") (pintype "passive"))
      (node (ref "U1") (pin "127") (pinfunction "PG12/FSMC_NE4_127") (pintype "passive"))
    )
    (net (code "48") (name "/FSMC_NOE") (class "Default")
      (node (ref "TFT1") (pin "7") (pinfunction "RD_7") (pintype "passive"))
      (node (ref "U1") (pin "118") (pinfunction "PD4/FSMC_NOE_118") (pintype "passive"))
      (node (ref "U2") (pin "41") (pinfunction "OE_41") (pintype "passive"))
    )
    (net (code "49") (name "/FSMC_NWE") (class "Default")
      (node (ref "TFT1") (pin "6") (pinfunction "WR_6") (pintype "passive"))
      (node (ref "U1") (pin "119") (pinfunction "PD5/FSMC_NWE_119") (pintype "passive"))
      (node (ref "U2") (pin "17") (pinfunction "WE_17") (pintype "passive"))
    )
    (net (code "50") (name "/F_CS") (class "Default")
      (node (ref "U1") (pin "73") (pinfunction "PB12/SPI2_NSS/I2S2_WS/I2C2_SMBAI/USART3_CK/TIM1BKIN_73") (pintype "passive"))
      (node (ref "U4") (pin "1") (pinfunction "CS_1") (pintype "passive"))
    )
    (net (code "51") (name "/IIC_SCL") (class "Default")
      (node (ref "U1") (pin "136") (pinfunction "PB6/I2C1_SCL/TIM4_CH1_136") (pintype "passive"))
      (node (ref "U3") (pin "6") (pinfunction "SCL_6") (pintype "passive"))
    )
    (net (code "52") (name "/IIC_SDA") (class "Default")
      (node (ref "U1") (pin "137") (pinfunction "PB7/I2C1_SDA/FSMC_NADV/TIM4_CH2_137") (pintype "passive"))
      (node (ref "U3") (pin "5") (pinfunction "SDA_5") (pintype "passive"))
    )
    (net (code "53") (name "/IOVDD") (class "Default")
      (node (ref "C74") (pin "2") (pintype "passive"))
      (node (ref "C75") (pin "2") (pintype "passive"))
      (node (ref "C76") (pin "2") (pintype "passive"))
      (node (ref "R67") (pin "1") (pintype "passive"))
      (node (ref "R68") (pin "2") (pintype "passive"))
      (node (ref "U19") (pin "14") (pinfunction "IOVDD_14") (pintype "passive"))
      (node (ref "U19") (pin "19") (pinfunction "IOVDD_19") (pintype "passive"))
      (node (ref "U19") (pin "32") (pinfunction "TEST_32") (pintype "passive"))
      (node (ref "U19") (pin "6") (pinfunction "IOVDD_6") (pintype "passive"))
    )
    (net (code "54") (name "/JTCK") (class "Default")
      (node (ref "P10") (pin "2") (pinfunction "2_2") (pintype "passive"))
      (node (ref "R6") (pin "1") (pintype "passive"))
      (node (ref "U1") (pin "109") (pinfunction "PA14/JTCK_SWCLK_109") (pintype "passive"))
    )
    (net (code "55") (name "/JTDO") (class "Default")
      (node (ref "U1") (pin "133") (pinfunction "PB3/JTDO/TRACESWO/SPI3_SCK/I2S3_CK_133") (pintype "passive"))
    )
    (net (code "56") (name "/JTMS") (class "Default")
      (node (ref "P10") (pin "3") (pinfunction "3_3") (pintype "passive"))
      (node (ref "R5") (pin "1") (pintype "passive"))
      (node (ref "U1") (pin "105") (pinfunction "PA13/JTMS_SWDIO_105") (pintype "passive"))
    )
    (net (code "57") (name "/JTRST") (class "Default")
      (node (ref "U1") (pin "134") (pinfunction "PB4/JNTRST/SPI3_MISO_134") (pintype "passive"))
    )
    (net (code "58") (name "/KEY0") (class "Default")
      (node (ref "KEY0") (pin "1") (pinfunction "1_1") (pintype "passive"))
      (node (ref "U1") (pin "5") (pinfunction "PE6/TRACED3/FSMC_A22_5") (pintype "passive"))
    )
    (net (code "59") (name "/KEY1") (class "Default")
      (node (ref "U1") (pin "35") (pinfunction "PA1/USART2_RTS/ADC123_IN1/TIM5_CH2/TIM2_CH2_35") (pintype "passive"))
    )
    (net (code "60") (name "/LCD_BL") (class "Default")
      (node (ref "R45") (pin "2") (pintype "passive"))
      (node (ref "U1") (pin "40") (pinfunction "PA4/SPI1_NSS/DAC_OUT1/USART2_CK/ADC12_IN4_40") (pintype "passive"))
    )
    (net (code "61") (name "/LED1") (class "Default")
      (node (ref "DS1") (pin "2") (pinfunction "K_2") (pintype "passive"))
      (node (ref "U1") (pin "91") (pinfunction "PG6/FSMC_INT2_91") (pintype "passive"))
    )
    (net (code "62") (name "/LED_A") (class "Default")
      (node (ref "C105") (pin "1") (pintype "passive"))
      (node (ref "D3") (pin "2") (pintype "passive"))
      (node (ref "TFT1") (pin "35") (pinfunction "LED_A_35") (pintype "passive"))
    )
    (net (code "63") (name "/LED_K") (class "Default")
      (node (ref "R44") (pin "2") (pintype "passive"))
      (node (ref "TFT1") (pin "34") (pinfunction "LED_K_34") (pintype "passive"))
      (node (ref "U16") (pin "3") (pinfunction "FB_3") (pintype "passive"))
    )
    (net (code "64") (name "/PA0") (class "Default")
      (node (ref "U1") (pin "34") (pinfunction "PA0-WKUP/USART2_CTS/ADC123_IN0/TIM5_CH1/TIM2_CH1_ETR/TIM8_ETR_34") (pintype "passive"))
    )
    (net (code "65") (name "/PA2") (class "Default")
      (node (ref "U1") (pin "36") (pinfunction "PA2/USART2_TX/ADC123_IN2/TIM5_CH3/TIM2_CH3_36") (pintype "passive"))
    )
    (net (code "66") (name "/PA3") (class "Default")
      (node (ref "U1") (pin "37") (pinfunction "PA3/USART2_RX/ADC123_IN3/TIM5_CH4/TIM2_CH4_37") (pintype "passive"))
    )
    (net (code "67") (name "/PA5") (class "Default")
      (node (ref "U1") (pin "41") (pinfunction "PA5/SPI1_SCK/DAC_OUT2/ADC12_IN5_41") (pintype "passive"))
      (node (ref "U19") (pin "28") (pinfunction "SCLK_28") (pintype "passive"))
    )
    (net (code "68") (name "/PA6") (class "Default")
      (node (ref "U1") (pin "42") (pinfunction "PA6/SPI1_MISO/TIM8_BKIN/ADC12_IN6/TIM3_CH1_42") (pintype "passive"))
      (node (ref "U19") (pin "30") (pinfunction "SO_30") (pintype "passive"))
    )
    (net (code "69") (name "/PA7") (class "Default")
      (node (ref "U1") (pin "43") (pinfunction "PA7/SPI1_MOSI/TIM8_CH1N/ADC12_IN7/TIM3_CH2_43") (pintype "passive"))
      (node (ref "U19") (pin "29") (pinfunction "S1_29") (pintype "passive"))
    )
    (net (code "70") (name "/PA8") (class "Default")
      (node (ref "U1") (pin "100") (pinfunction "PA8/USART1_CK/TIM1_CH1/MCO_100") (pintype "passive"))
    )
    (net (code "71") (name "/PA9") (class "Default")
      (node (ref "U1") (pin "101") (pinfunction "PA9/USART1_TX/TIM1_CH2_101") (pintype "passive"))
    )
    (net (code "72") (name "/PA10") (class "Default")
      (node (ref "U1") (pin "102") (pinfunction "PA10/USART1_RX/TIM1_CH3_102") (pintype "passive"))
    )
    (net (code "73") (name "/PA11") (class "Default")
      (node (ref "R33") (pin "2") (pintype "passive"))
      (node (ref "U1") (pin "103") (pinfunction "PA11/USART1_CTS/CAN_RX/TIM1_CH4/USBDM_103") (pintype "passive"))
    )
    (net (code "74") (name "/PA12") (class "Default")
      (node (ref "R32") (pin "2") (pintype "passive"))
      (node (ref "U1") (pin "104") (pinfunction "PA12/USART1_RTS/CAN_TX/TIM1_ETR/USBDP_104") (pintype "passive"))
    )
    (net (code "75") (name "/PA15") (class "Default")
      (node (ref "U1") (pin "110") (pinfunction "PA15/JTDI/SPI3_NSS/I2S3_WS_110") (pintype "passive"))
    )
    (net (code "76") (name "/PB0") (class "Default")
      (node (ref "J3") (pin "3") (pinfunction "INT_3") (pintype "passive"))
      (node (ref "U1") (pin "46") (pinfunction "PB0/ADC12_IN8/TIM3_CH3/TIM8_CH2N_46") (pintype "passive"))
    )
    (net (code "77") (name "/PB1") (class "Default")
      (node (ref "J3") (pin "2") (pinfunction "RST_2") (pintype "passive"))
      (node (ref "U1") (pin "47") (pinfunction "PB1/ADC12_IN9/TIM3_CH4/TIM8_CH3N_47") (pintype "passive"))
    )
    (net (code "78") (name "/PB5") (class "Default")
      (node (ref "U1") (pin "135") (pinfunction "PB5/I2C1_SMBAI/SPI3_MOSI/I2S3_SD_135") (pintype "passive"))
    )
    (net (code "79") (name "/PB8") (class "Default")
      (node (ref "U1") (pin "139") (pinfunction "PB8/TIM4_CH3/SDIO_D4_139") (pintype "passive"))
    )
    (net (code "80") (name "/PB9") (class "Default")
      (node (ref "U1") (pin "140") (pinfunction "PB9/TIM4_CH4/SDIO_D5_140") (pintype "passive"))
    )
    (net (code "81") (name "/PB10") (class "Default")
      (node (ref "U1") (pin "69") (pinfunction "PB10/I2C2_SCL/USART3_TX_69") (pintype "passive"))
    )
    (net (code "82") (name "/PB11") (class "Default")
      (node (ref "U1") (pin "70") (pinfunction "PB11/I2C2_SDA/USART3_RX_70") (pintype "passive"))
    )
    (net (code "83") (name "/PB13") (class "Default")
      (node (ref "U1") (pin "74") (pinfunction "PB13/SPI2_SCK/I2S2_CK/USART3_CTS/TIM1_CH1N_74") (pintype "passive"))
      (node (ref "U4") (pin "6") (pinfunction "CLK_6") (pintype "passive"))
    )
    (net (code "84") (name "/PB14") (class "Default")
      (node (ref "U1") (pin "75") (pinfunction "PB14/SPI2_MISO/USART3_RTS/TIM1_CH2N_75") (pintype "passive"))
      (node (ref "U4") (pin "2") (pinfunction "SO_2") (pintype "passive"))
    )
    (net (code "85") (name "/PB15") (class "Default")
      (node (ref "U1") (pin "76") (pinfunction "PB15/SPI2_MOSI/I2S2_SD/TIM1_CH3N_76") (pintype "passive"))
      (node (ref "U4") (pin "5") (pinfunction "SI_5") (pintype "passive"))
    )
    (net (code "86") (name "/PC0") (class "Default")
      (node (ref "U1") (pin "26") (pinfunction "PC0/ADC123_IN10_26") (pintype "passive"))
    )
    (net (code "87") (name "/PC1") (class "Default")
      (node (ref "U1") (pin "27") (pinfunction "PC1/ADC123_IN11_27") (pintype "passive"))
    )
    (net (code "88") (name "/PC2") (class "Default")
      (node (ref "U1") (pin "28") (pinfunction "PC2/ADC123_IN12_28") (pintype "passive"))
    )
    (net (code "89") (name "/PC3") (class "Default")
      (node (ref "U1") (pin "29") (pinfunction "PC3/ADC123_IN13_29") (pintype "passive"))
    )
    (net (code "90") (name "/PC4") (class "Default")
      (node (ref "J3") (pin "7") (pinfunction "SDA_7") (pintype "passive"))
      (node (ref "U1") (pin "44") (pinfunction "PC4/ADC12_IN14_44") (pintype "passive"))
    )
    (net (code "91") (name "/PC5") (class "Default")
      (node (ref "J3") (pin "6") (pinfunction "SCL_6") (pintype "passive"))
      (node (ref "U1") (pin "45") (pinfunction "PC5/ADC12_IN15_45") (pintype "passive"))
    )
    (net (code "92") (name "/PC6") (class "Default")
      (node (ref "U1") (pin "96") (pinfunction "PC6/I2S2_MCK/TIM8_CH1/SDIO_D6_96") (pintype "passive"))
    )
    (net (code "93") (name "/PC7") (class "Default")
      (node (ref "U1") (pin "97") (pinfunction "PC7/I2S3_MCK/TIM8_CH2/SDIO_D7_97") (pintype "passive"))
    )
    (net (code "94") (name "/PC8") (class "Default")
      (node (ref "R15") (pin "1") (pintype "passive"))
      (node (ref "TF_CARD") (pin "7") (pinfunction "DAT0/DO_7") (pintype "passive"))
      (node (ref "U1") (pin "98") (pinfunction "PC8/TIM8_CH3/SDIO_D0_98") (pintype "passive"))
    )
    (net (code "95") (name "/PC9") (class "Default")
      (node (ref "R19") (pin "1") (pintype "passive"))
      (node (ref "TF_CARD") (pin "8") (pinfunction "DAT1/IRQ_8") (pintype "passive"))
      (node (ref "U1") (pin "99") (pinfunction "PC9/TIM8_CH4/SDIO_D1_99") (pintype "passive"))
    )
    (net (code "96") (name "/PC10") (class "Default")
      (node (ref "R18") (pin "1") (pintype "passive"))
      (node (ref "TF_CARD") (pin "1") (pinfunction "DAT2/NC_1") (pintype "passive"))
      (node (ref "U1") (pin "111") (pinfunction "PC10/UART4_TX/SDIO_D2_111") (pintype "passive"))
    )
    (net (code "97") (name "/PC11") (class "Default")
      (node (ref "R17") (pin "1") (pintype "passive"))
      (node (ref "TF_CARD") (pin "2") (pinfunction "CS/DATA3_2") (pintype "passive"))
      (node (ref "U1") (pin "112") (pinfunction "PC11/UART4_RX/SDIO_D3_112") (pintype "passive"))
    )
    (net (code "98") (name "/PC12") (class "Default")
      (node (ref "TF_CARD") (pin "5") (pinfunction "CLK_5") (pintype "passive"))
      (node (ref "U1") (pin "113") (pinfunction "PC12/UART5_TX/SDIO_CK_113") (pintype "passive"))
    )
    (net (code "99") (name "/PC13") (class "Default")
      (node (ref "U1") (pin "7") (pinfunction "PC13-TAMPER-RTC_7") (pintype "passive"))
    )
    (net (code "100") (name "/PC14") (class "Default")
      (node (ref "C3") (pin "2") (pintype "passive"))
      (node (ref "U1") (pin "8") (pinfunction "PC14-OSC32_IN_8") (pintype "passive"))
      (node (ref "Y2") (pin "1") (pinfunction "OSC1_1") (pintype "passive"))
    )
    (net (code "101") (name "/PC15") (class "Default")
      (node (ref "C4") (pin "1") (pintype "passive"))
      (node (ref "U1") (pin "9") (pinfunction "PC15-OSC32_OUT_9") (pintype "passive"))
      (node (ref "Y2") (pin "2") (pinfunction "OSC2_2") (pintype "passive"))
    )
    (net (code "102") (name "/PD2") (class "Default")
      (node (ref "R16") (pin "1") (pintype "passive"))
      (node (ref "TF_CARD") (pin "3") (pinfunction "CMD_3") (pintype "passive"))
      (node (ref "U1") (pin "116") (pinfunction "PD2/TIM3_ETR/UART5_RX/SDIO_CMD_116") (pintype "passive"))
    )
    (net (code "103") (name "/PD3") (class "Default")
      (node (ref "U1") (pin "117") (pinfunction "PD3/FSMC_CLK_117") (pintype "passive"))
    )
    (net (code "104") (name "/PD6") (class "Default")
      (node (ref "U1") (pin "122") (pinfunction "PD6/FSMC_NWAIT_122") (pintype "passive"))
    )
    (net (code "105") (name "/PD7") (class "Default")
      (node (ref "U1") (pin "123") (pinfunction "PD7/FSMC_NE1/FSMC_NCE2_123") (pintype "passive"))
    )
    (net (code "106") (name "/PE2") (class "Default")
      (node (ref "U1") (pin "1") (pinfunction "PE2/TRACECK/FSMC_A23_1") (pintype "passive"))
      (node (ref "U19") (pin "8") (pinfunction "DREQ_8") (pintype "passive"))
    )
    (net (code "107") (name "/PE3") (class "Default")
      (node (ref "U1") (pin "2") (pinfunction "PE3/TRACED0/FSMC_A19_2") (pintype "passive"))
      (node (ref "U19") (pin "3") (pinfunction "XREST_3") (pintype "passive"))
    )
    (net (code "108") (name "/PE4") (class "Default")
      (node (ref "U1") (pin "3") (pinfunction "PE4/TRACED1/FSMC_A20_3") (pintype "passive"))
      (node (ref "U19") (pin "23") (pinfunction "XCS_23") (pintype "passive"))
    )
    (net (code "109") (name "/PE5") (class "Default")
      (node (ref "U1") (pin "4") (pinfunction "PE5/TRACED2/FSMC_A21_4") (pintype "passive"))
      (node (ref "U19") (pin "13") (pinfunction "XDCS/BSYNC_13") (pintype "passive"))
    )
    (net (code "110") (name "/PF6") (class "Default")
      (node (ref "U1") (pin "18") (pinfunction "PF6/ADC3_IN4/FSMC_NIORD_18") (pintype "passive"))
    )
    (net (code "111") (name "/PF7") (class "Default")
      (node (ref "U1") (pin "19") (pinfunction "PF7/ADC3_IN5/FSMC_NREG_19") (pintype "passive"))
    )
    (net (code "112") (name "/PF8") (class "Default")
      (node (ref "U1") (pin "20") (pinfunction "PF8/ADC3_IN6/FSMC_NIOWR_20") (pintype "passive"))
    )
    (net (code "113") (name "/PF9") (class "Default")
      (node (ref "U1") (pin "21") (pinfunction "PF9/ADC3_IN7/FSMC_CD_21") (pintype "passive"))
    )
    (net (code "114") (name "/PF10") (class "Default")
      (node (ref "U1") (pin "22") (pinfunction "PF10/ADC3_IN8/FSMC_INTR_22") (pintype "passive"))
    )
    (net (code "115") (name "/PF11") (class "Default")
      (node (ref "U1") (pin "49") (pinfunction "PF11/FSMC_NIOS16_49") (pintype "passive"))
    )
    (net (code "116") (name "/PG7") (class "Default")
      (node (ref "U1") (pin "92") (pinfunction "PG7/FSMC_INT3_92") (pintype "passive"))
    )
    (net (code "117") (name "/PG8") (class "Default")
      (node (ref "U1") (pin "93") (pinfunction "PG8_93") (pintype "passive"))
    )
    (net (code "118") (name "/PG9") (class "Default")
      (node (ref "U1") (pin "124") (pinfunction "PG9/FSMC_NE2/FSMC_NCE3_124") (pintype "passive"))
    )
    (net (code "119") (name "/PG11") (class "Default")
      (node (ref "U1") (pin "126") (pinfunction "PG11/FSMC_NCE4_2_126") (pintype "passive"))
    )
    (net (code "120") (name "/PG13") (class "Default")
      (node (ref "U1") (pin "128") (pinfunction "PG13/FSMC_A24_128") (pintype "passive"))
    )
    (net (code "121") (name "/PG15") (class "Default")
      (node (ref "U1") (pin "132") (pinfunction "PG15_132") (pintype "passive"))
    )
    (net (code "122") (name "/PJ_G") (class "Default")
      (node (ref "PJ1") (pin "7") (pinfunction "7_7") (pintype "passive"))
    )
    (net (code "123") (name "/PJ_L") (class "Default")
      (node (ref "PJ1") (pin "5") (pinfunction "L_5") (pintype "passive"))
    )
    (net (code "124") (name "/PJ_M") (class "Default")
      (node (ref "PJ1") (pin "8") (pinfunction "8_8") (pintype "passive"))
    )
    (net (code "125") (name "/PJ_R") (class "Default")
      (node (ref "PJ1") (pin "6") (pinfunction "6_6") (pintype "passive"))
    )
    (net (code "126") (name "/RESET") (class "Default")
      (node (ref "C10") (pin "2") (pintype "passive"))
      (node (ref "R3") (pin "1") (pintype "passive"))
      (node (ref "RESET") (pin "1") (pinfunction "1_1") (pintype "passive"))
      (node (ref "TFT1") (pin "8") (pinfunction "RST_8") (pintype "passive"))
      (node (ref "U1") (pin "25") (pinfunction "NRST_25") (pintype "passive"))
    )
    (net (code "127") (name "/SPK_CTRL") (class "Default")
      (node (ref "R53") (pin "2") (pintype "passive"))
      (node (ref "U17") (pin "1") (pinfunction "CTRL_1") (pintype "passive"))
      (node (ref "U19") (pin "36") (pinfunction "GPIO4/I2S_LROUT_36") (pintype "passive"))
    )
    (net (code "128") (name "/VUSB") (class "Default")
      (node (ref "POWER") (pin "3") (pinfunction "I/O_3") (pintype "passive"))
      (node (ref "USB_HOST") (pin "1") (pinfunction "VCC_1") (pintype "passive"))
    )
    (net (code "129") (name "GND") (class "Default")
      (node (ref "BAT") (pin "2") (pinfunction "GND_2") (pintype "passive"))
      (node (ref "C1") (pin "1") (pintype "passive"))
      (node (ref "C10") (pin "1") (pintype "passive"))
      (node (ref "C100") (pin "1") (pintype "passive"))
      (node (ref "C101") (pin "1") (pintype "passive"))
      (node (ref "C102") (pin "1") (pintype "passive"))
      (node (ref "C103") (pin "1") (pintype "passive"))
      (node (ref "C104") (pin "1") (pintype "passive"))
      (node (ref "C105") (pin "2") (pintype "passive"))
      (node (ref "C11") (pin "1") (pintype "passive"))
      (node (ref "C12") (pin "1") (pintype "passive"))
      (node (ref "C13") (pin "1") (pintype "passive"))
      (node (ref "C14") (pin "1") (pintype "passive"))
      (node (ref "C15") (pin "1") (pintype "passive"))
      (node (ref "C16") (pin "1") (pintype "passive"))
      (node (ref "C17") (pin "1") (pintype "passive"))
      (node (ref "C18") (pin "1") (pintype "passive"))
      (node (ref "C19") (pin "1") (pintype "passive"))
      (node (ref "C2") (pin "1") (pintype "passive"))
      (node (ref "C20") (pin "1") (pintype "passive"))
      (node (ref "C21") (pin "1") (pintype "passive"))
      (node (ref "C29") (pin "2") (pintype "passive"))
      (node (ref "C3") (pin "1") (pintype "passive"))
      (node (ref "C31") (pin "2") (pintype "passive"))
      (node (ref "C36") (pin "2") (pintype "passive"))
      (node (ref "C4") (pin "2") (pintype "passive"))
      (node (ref "C42") (pin "1") (pintype "passive"))
      (node (ref "C43") (pin "1") (pintype "passive"))
      (node (ref "C44") (pin "2") (pinfunction "GND_2") (pintype "passive"))
      (node (ref "C45") (pin "1") (pintype "passive"))
      (node (ref "C5") (pin "1") (pintype "passive"))
      (node (ref "C54") (pin "2") (pintype "passive"))
      (node (ref "C6") (pin "1") (pintype "passive"))
      (node (ref "C60") (pin "1") (pintype "passive"))
      (node (ref "C61") (pin "1") (pintype "passive"))
      (node (ref "C62") (pin "1") (pintype "passive"))
      (node (ref "C65") (pin "1") (pintype "passive"))
      (node (ref "C66") (pin "1") (pintype "passive"))
      (node (ref "C67") (pin "1") (pintype "passive"))
      (node (ref "C7") (pin "1") (pintype "passive"))
      (node (ref "C72") (pin "1") (pintype "passive"))
      (node (ref "C74") (pin "1") (pintype "passive"))
      (node (ref "C75") (pin "1") (pintype "passive"))
      (node (ref "C76") (pin "1") (pintype "passive"))
      (node (ref "C77") (pin "2") (pintype "passive"))
      (node (ref "C78") (pin "2") (pintype "passive"))
      (node (ref "C79") (pin "2") (pintype "passive"))
      (node (ref "C8") (pin "1") (pintype "passive"))
      (node (ref "C80") (pin "1") (pintype "passive"))
      (node (ref "C87") (pin "1") (pintype "passive"))
      (node (ref "C88") (pin "1") (pintype "passive"))
      (node (ref "C89") (pin "1") (pintype "passive"))
      (node (ref "C9") (pin "1") (pintype "passive"))
      (node (ref "C91") (pin "1") (pintype "passive"))
      (node (ref "C92") (pin "1") (pintype "passive"))
      (node (ref "C93") (pin "1") (pintype "passive"))
      (node (ref "C94") (pin "2") (pintype "passive"))
      (node (ref "C97") (pin "1") (pintype "passive"))
      (node (ref "C98") (pin "1") (pintype "passive"))
      (node (ref "J3") (pin "8") (pinfunction "GND_8") (pintype "passive"))
      (node (ref "KEY0") (pin "2") (pinfunction "2_2") (pintype "passive"))
      (node (ref "P10") (pin "1") (pinfunction "1_1") (pintype "passive"))
      (node (ref "R11") (pin "2") (pintype "passive"))
      (node (ref "R44") (pin "1") (pintype "passive"))
      (node (ref "R46") (pin "2") (pintype "passive"))
      (node (ref "R53") (pin "1") (pintype "passive"))
      (node (ref "R6") (pin "2") (pintype "passive"))
      (node (ref "R70") (pin "1") (pintype "passive"))
      (node (ref "R76") (pin "2") (pintype "passive"))
      (node (ref "RESET") (pin "2") (pinfunction "2_2") (pintype "passive"))
      (node (ref "TFT1") (pin "1") (pinfunction "GND_1") (pintype "passive"))
      (node (ref "TFT1") (pin "37") (pinfunction "GND_37") (pintype "passive"))
      (node (ref "TF_CARD") (pin "6") (pinfunction "VSS_6") (pintype "passive"))
      (node (ref "U1") (pin "107") (pinfunction "VSS_107") (pintype "passive"))
      (node (ref "U1") (pin "120") (pinfunction "VSS_120") (pintype "passive"))
      (node (ref "U1") (pin "130") (pinfunction "VSS_130") (pintype "passive"))
      (node (ref "U1") (pin "143") (pinfunction "VSS_143") (pintype "passive"))
      (node (ref "U1") (pin "16") (pinfunction "VSS_16") (pintype "passive"))
      (node (ref "U1") (pin "30") (pinfunction "VSSA_30") (pintype "passive"))
      (node (ref "U1") (pin "31") (pinfunction "Vref-_31") (pintype "passive"))
      (node (ref "U1") (pin "38") (pinfunction "VSS_38") (pintype "passive"))
      (node (ref "U1") (pin "51") (pinfunction "VSS_51") (pintype "passive"))
      (node (ref "U1") (pin "61") (pinfunction "VSS_61") (pintype "passive"))
      (node (ref "U1") (pin "71") (pinfunction "VSS_71") (pintype "passive"))
      (node (ref "U1") (pin "83") (pinfunction "VSS_83") (pintype "passive"))
      (node (ref "U1") (pin "94") (pinfunction "VSS_94") (pintype "passive"))
      (node (ref "U12") (pin "1") (pinfunction "GND_1") (pintype "passive"))
      (node (ref "U15") (pin "1") (pinfunction "GND_1") (pintype "passive"))
      (node (ref "U16") (pin "2") (pinfunction "GND_2") (pintype "passive"))
      (node (ref "U17") (pin "7") (pinfunction "GND_7") (pintype "passive"))
      (node (ref "U19") (pin "16") (pinfunction "DGND_16") (pintype "passive"))
      (node (ref "U19") (pin "20") (pinfunction "DGND_20") (pintype "passive"))
      (node (ref "U19") (pin "21") (pinfunction "DGND_21") (pintype "passive"))
      (node (ref "U19") (pin "22") (pinfunction "DGND_22") (pintype "passive"))
      (node (ref "U19") (pin "35") (pinfunction "DGND_35") (pintype "passive"))
      (node (ref "U19") (pin "37") (pinfunction "AGND_37") (pintype "passive"))
      (node (ref "U19") (pin "4") (pinfunction "DGND_4") (pintype "passive"))
      (node (ref "U19") (pin "40") (pinfunction "AGND_40") (pintype "passive"))
      (node (ref "U19") (pin "41") (pinfunction "AGND_41") (pintype "passive"))
      (node (ref "U19") (pin "47") (pinfunction "AGND_47") (pintype "passive"))
      (node (ref "U2") (pin "12") (pinfunction "GND_12") (pintype "passive"))
      (node (ref "U2") (pin "34") (pinfunction "GND_34") (pintype "passive"))
      (node (ref "U3") (pin "1") (pinfunction "A0_1") (pintype "passive"))
      (node (ref "U3") (pin "2") (pinfunction "A1_2") (pintype "passive"))
      (node (ref "U3") (pin "3") (pinfunction "A2_3") (pintype "passive"))
      (node (ref "U3") (pin "4") (pinfunction "GND_4") (pintype "passive"))
      (node (ref "U3") (pin "7") (pinfunction "WP_7") (pintype "passive"))
      (node (ref "U4") (pin "4") (pinfunction "GND_4") (pintype "passive"))
      (node (ref "USB_HOST") (pin "5") (pinfunction "GND_5") (pintype "passive"))
      (node (ref "USB_HOST") (pin "6") (pinfunction "Shell1_6") (pintype "passive"))
      (node (ref "USB_HOST") (pin "7") (pinfunction "Shell2_7") (pintype "passive"))
      (node (ref "USB_HOST") (pin "8") (pinfunction "Shell3_8") (pintype "passive"))
      (node (ref "USB_HOST") (pin "9") (pinfunction "Shell4_9") (pintype "passive"))
      (node (ref "Y1") (pin "2") (pinfunction "GND_2") (pintype "passive"))
      (node (ref "Y4") (pin "2") (pinfunction "GND_2") (pintype "passive"))
      (node (ref "Y4") (pin "4") (pinfunction "GND_4") (pintype "passive"))
    )
    (net (code "130") (name "Net-(BAT-VCC)") (class "Default")
      (node (ref "BAT") (pin "1") (pinfunction "VCC_1") (pintype "passive"))
      (node (ref "D2") (pin "1") (pintype "passive"))
    )
    (net (code "131") (name "Net-(C60-Pad2)") (class "Default")
      (node (ref "C60") (pin "2") (pintype "passive"))
      (node (ref "R50") (pin "1") (pintype "passive"))
    )
    (net (code "132") (name "Net-(C61-Pad2)") (class "Default")
      (node (ref "C61") (pin "2") (pintype "passive"))
      (node (ref "R51") (pin "1") (pintype "passive"))
    )
    (net (code "133") (name "Net-(C62-Pad2)") (class "Default")
      (node (ref "C62") (pin "2") (pintype "passive"))
      (node (ref "R52") (pin "1") (pintype "passive"))
    )
    (net (code "134") (name "Net-(C72-Pad2)") (class "Default")
      (node (ref "C72") (pin "2") (pintype "passive"))
      (node (ref "R58") (pin "1") (pintype "passive"))
    )
    (net (code "135") (name "Net-(C73-Pad2)") (class "Default")
      (node (ref "C73") (pin "2") (pintype "passive"))
      (node (ref "R61") (pin "1") (pintype "passive"))
    )
    (net (code "136") (name "Net-(C77-Pad1)") (class "Default")
      (node (ref "C77") (pin "1") (pintype "passive"))
      (node (ref "C78") (pin "1") (pintype "passive"))
      (node (ref "C79") (pin "1") (pintype "passive"))
      (node (ref "C80") (pin "2") (pintype "passive"))
      (node (ref "U15") (pin "2") (pinfunction "OUT_2") (pintype "passive"))
      (node (ref "U15") (pin "4") (pinfunction "OUT_4") (pintype "passive"))
      (node (ref "U19") (pin "24") (pinfunction "CVDD_24") (pintype "passive"))
      (node (ref "U19") (pin "31") (pinfunction "CVDD_31") (pintype "passive"))
      (node (ref "U19") (pin "5") (pinfunction "CVDD_5") (pintype "passive"))
      (node (ref "U19") (pin "7") (pinfunction "CVDD_7") (pintype "passive"))
    )
    (net (code "137") (name "Net-(C89-Pad2)") (class "Default")
      (node (ref "C89") (pin "2") (pintype "passive"))
      (node (ref "C90") (pin "2") (pintype "passive"))
      (node (ref "R71") (pin "1") (pintype "passive"))
      (node (ref "R73") (pin "2") (pintype "passive"))
    )
    (net (code "138") (name "Net-(C90-Pad1)") (class "Default")
      (node (ref "C90") (pin "1") (pintype "passive"))
      (node (ref "R75") (pin "1") (pintype "passive"))
      (node (ref "R76") (pin "1") (pintype "passive"))
    )
    (net (code "139") (name "Net-(DS1-A)") (class "Default")
      (node (ref "DS1") (pin "1") (pinfunction "A_1") (pintype "passive"))
      (node (ref "R20") (pin "2") (pintype "passive"))
    )
    (net (code "140") (name "Net-(J3-VDD)") (class "Default")
      (node (ref "C101") (pin "2") (pintype "passive"))
      (node (ref "C102") (pin "2") (pintype "passive"))
      (node (ref "J3") (pin "1") (pinfunction "VDD_1") (pintype "passive"))
      (node (ref "R47") (pin "1") (pintype "passive"))
    )
    (net (code "141") (name "Net-(MIC-GND)") (class "Default")
      (node (ref "C96") (pin "1") (pintype "passive"))
      (node (ref "C99") (pin "2") (pintype "passive"))
      (node (ref "MIC") (pin "2") (pinfunction "GND_2") (pintype "passive"))
      (node (ref "R75") (pin "2") (pintype "passive"))
    )
    (net (code "142") (name "Net-(MIC-VCC)") (class "Default")
      (node (ref "C95") (pin "1") (pintype "passive"))
      (node (ref "C96") (pin "2") (pintype "passive"))
      (node (ref "MIC") (pin "1") (pinfunction "VCC_1") (pintype "passive"))
      (node (ref "R73") (pin "1") (pintype "passive"))
    )
    (net (code "143") (name "Net-(U1-OSC_IN)") (class "Default")
      (node (ref "C7") (pin "2") (pintype "passive"))
      (node (ref "U1") (pin "23") (pinfunction "OSC_IN_23") (pintype "passive"))
      (node (ref "Y1") (pin "3") (pinfunction "OSC2_3") (pintype "passive"))
    )
    (net (code "144") (name "Net-(U1-OSC_OUT)") (class "Default")
      (node (ref "C6") (pin "2") (pintype "passive"))
      (node (ref "U1") (pin "24") (pinfunction "OSC_OUT_24") (pintype "passive"))
      (node (ref "Y1") (pin "1") (pinfunction "OSC1_1") (pintype "passive"))
    )
    (net (code "145") (name "Net-(U1-VBAT)") (class "Default")
      (node (ref "C5") (pin "2") (pintype "passive"))
      (node (ref "D1") (pin "2") (pintype "passive"))
      (node (ref "D2") (pin "2") (pintype "passive"))
      (node (ref "U1") (pin "6") (pinfunction "VBAT_6") (pintype "passive"))
    )
    (net (code "146") (name "Net-(U1-VDDA)") (class "Default")
      (node (ref "C8") (pin "2") (pintype "passive"))
      (node (ref "C9") (pin "2") (pintype "passive"))
      (node (ref "R4") (pin "1") (pintype "passive"))
      (node (ref "U1") (pin "32") (pinfunction "Vref+_32") (pintype "passive"))
      (node (ref "U1") (pin "33") (pinfunction "VDDA_33") (pintype "passive"))
    )
    (net (code "147") (name "Net-(U16-EN)") (class "Default")
      (node (ref "R45") (pin "1") (pintype "passive"))
      (node (ref "R46") (pin "1") (pintype "passive"))
      (node (ref "U16") (pin "4") (pinfunction "EN_4") (pintype "passive"))
    )
    (net (code "148") (name "Net-(U16-IN)") (class "Default")
      (node (ref "C98") (pin "2") (pintype "passive"))
      (node (ref "R43") (pin "1") (pintype "passive"))
      (node (ref "U16") (pin "5") (pinfunction "IN_5") (pintype "passive"))
    )
    (net (code "149") (name "Net-(U16-SW)") (class "Default")
      (node (ref "D3") (pin "1") (pintype "passive"))
      (node (ref "L7") (pin "1") (pintype "passive"))
      (node (ref "U16") (pin "1") (pinfunction "SW_1") (pintype "passive"))
    )
    (net (code "150") (name "Net-(U17-BYPASS)") (class "Default")
      (node (ref "C67") (pin "2") (pintype "passive"))
      (node (ref "U17") (pin "2") (pinfunction "BYPASS_2") (pintype "passive"))
    )
    (net (code "151") (name "Net-(U17-IN+)") (class "Default")
      (node (ref "R61") (pin "2") (pintype "passive"))
      (node (ref "U17") (pin "4") (pinfunction "IN+_4") (pintype "passive"))
    )
    (net (code "152") (name "Net-(U17-IN-)") (class "Default")
      (node (ref "R58") (pin "2") (pintype "passive"))
      (node (ref "U17") (pin "3") (pinfunction "IN-_3") (pintype "passive"))
    )
    (net (code "153") (name "Net-(U17-OUT+)") (class "Default")
      (node (ref "SP+") (pin "1") (pinfunction "1_1") (pintype "passive"))
      (node (ref "U17") (pin "5") (pinfunction "OUT+_5") (pintype "passive"))
    )
    (net (code "154") (name "Net-(U17-OUT-)") (class "Default")
      (node (ref "SP-") (pin "1") (pinfunction "1_1") (pintype "passive"))
      (node (ref "U17") (pin "8") (pinfunction "OUT-_8") (pintype "passive"))
    )
    (net (code "155") (name "Net-(U19-GPIO0)") (class "Default")
      (node (ref "R70") (pin "2") (pintype "passive"))
      (node (ref "U19") (pin "33") (pinfunction "GPIO0_33") (pintype "passive"))
      (node (ref "U19") (pin "34") (pinfunction "GPIO1_34") (pintype "passive"))
    )
    (net (code "156") (name "Net-(U19-LINE2)") (class "Default")
      (node (ref "C103") (pin "2") (pintype "passive"))
      (node (ref "U19") (pin "48") (pinfunction "LINE2_48") (pintype "passive"))
    )
    (net (code "157") (name "Net-(U19-MICN)") (class "Default")
      (node (ref "C99") (pin "1") (pintype "passive"))
      (node (ref "U19") (pin "2") (pinfunction "MICN_2") (pintype "passive"))
    )
    (net (code "158") (name "Net-(U19-MICP{slash}LINE1)") (class "Default")
      (node (ref "C104") (pin "2") (pintype "passive"))
      (node (ref "C95") (pin "2") (pintype "passive"))
      (node (ref "U19") (pin "1") (pinfunction "MICP/LINE1_1") (pintype "passive"))
    )
    (net (code "159") (name "Net-(U19-RCAP)") (class "Default")
      (node (ref "C94") (pin "1") (pintype "passive"))
      (node (ref "U19") (pin "44") (pinfunction "RCAP_44") (pintype "passive"))
    )
    (net (code "160") (name "Net-(U19-RX)") (class "Default")
      (node (ref "R68") (pin "1") (pintype "passive"))
      (node (ref "U19") (pin "26") (pinfunction "RX_26") (pintype "passive"))
    )
    (net (code "161") (name "Net-(U19-XIALO)") (class "Default")
      (node (ref "C88") (pin "2") (pintype "passive"))
      (node (ref "U19") (pin "17") (pinfunction "XIALO_17") (pintype "passive"))
      (node (ref "Y4") (pin "3") (pinfunction "HOT_3") (pintype "passive"))
    )
    (net (code "162") (name "Net-(U19-XTALI)") (class "Default")
      (node (ref "C87") (pin "2") (pintype "passive"))
      (node (ref "U19") (pin "18") (pinfunction "XTALI_18") (pintype "passive"))
      (node (ref "Y4") (pin "1") (pinfunction "HOT_1") (pintype "passive"))
    )
    (net (code "163") (name "Net-(USB_HOST-D+)") (class "Default")
      (node (ref "R32") (pin "1") (pintype "passive"))
      (node (ref "R35") (pin "1") (pintype "passive"))
      (node (ref "USB_HOST") (pin "3") (pinfunction "D+_3") (pintype "passive"))
    )
    (net (code "164") (name "Net-(USB_HOST-D-)") (class "Default")
      (node (ref "R33") (pin "1") (pintype "passive"))
      (node (ref "USB_HOST") (pin "2") (pinfunction "D-_2") (pintype "passive"))
    )
    (net (code "165") (name "VCC3.3") (class "Default")
      (node (ref "C1") (pin "2") (pintype "passive"))
      (node (ref "C100") (pin "2") (pintype "passive"))
      (node (ref "C11") (pin "2") (pintype "passive"))
      (node (ref "C12") (pin "2") (pintype "passive"))
      (node (ref "C13") (pin "2") (pintype "passive"))
      (node (ref "C14") (pin "2") (pintype "passive"))
      (node (ref "C15") (pin "2") (pintype "passive"))
      (node (ref "C16") (pin "2") (pintype "passive"))
      (node (ref "C17") (pin "2") (pintype "passive"))
      (node (ref "C18") (pin "2") (pintype "passive"))
      (node (ref "C19") (pin "2") (pintype "passive"))
      (node (ref "C2") (pin "2") (pintype "passive"))
      (node (ref "C20") (pin "2") (pintype "passive"))
      (node (ref "C21") (pin "2") (pintype "passive"))
      (node (ref "C29") (pin "1") (pintype "passive"))
      (node (ref "C31") (pin "1") (pintype "passive"))
      (node (ref "C36") (pin "1") (pintype "passive"))
      (node (ref "C43") (pin "2") (pintype "passive"))
      (node (ref "C44") (pin "1") (pinfunction "VCC_1") (pintype "passive"))
      (node (ref "D1") (pin "1") (pintype "passive"))
      (node (ref "P10") (pin "4") (pinfunction "4_4") (pintype "passive"))
      (node (ref "R1") (pin "2") (pintype "passive"))
      (node (ref "R15") (pin "2") (pintype "passive"))
      (node (ref "R16") (pin "2") (pintype "passive"))
      (node (ref "R17") (pin "2") (pintype "passive"))
      (node (ref "R18") (pin "2") (pintype "passive"))
      (node (ref "R19") (pin "2") (pintype "passive"))
      (node (ref "R20") (pin "1") (pintype "passive"))
      (node (ref "R3") (pin "2") (pintype "passive"))
      (node (ref "R35") (pin "2") (pintype "passive"))
      (node (ref "R4") (pin "2") (pintype "passive"))
      (node (ref "R42") (pin "2") (pintype "passive"))
      (node (ref "R47") (pin "2") (pintype "passive"))
      (node (ref "R5") (pin "2") (pintype "passive"))
      (node (ref "R67") (pin "2") (pintype "passive"))
      (node (ref "TFT1") (pin "2") (pinfunction "VDD_2") (pintype "passive"))
      (node (ref "TFT1") (pin "3") (pinfunction "IOVCC_3") (pintype "passive"))
      (node (ref "TF_CARD") (pin "4") (pinfunction "VDD_4") (pintype "passive"))
      (node (ref "U1") (pin "108") (pinfunction "VDD_108") (pintype "passive"))
      (node (ref "U1") (pin "121") (pinfunction "VDD_121") (pintype "passive"))
      (node (ref "U1") (pin "131") (pinfunction "VDD_131") (pintype "passive"))
      (node (ref "U1") (pin "144") (pinfunction "VDD_144") (pintype "passive"))
      (node (ref "U1") (pin "17") (pinfunction "VDD_17") (pintype "passive"))
      (node (ref "U1") (pin "39") (pinfunction "VDD_39") (pintype "passive"))
      (node (ref "U1") (pin "52") (pinfunction "VDD_52") (pintype "passive"))
      (node (ref "U1") (pin "62") (pinfunction "VDD_62") (pintype "passive"))
      (node (ref "U1") (pin "72") (pinfunction "VDD_72") (pintype "passive"))
      (node (ref "U1") (pin "84") (pinfunction "VDD_84") (pintype "passive"))
      (node (ref "U1") (pin "95") (pinfunction "VDD_95") (pintype "passive"))
      (node (ref "U12") (pin "2") (pinfunction "OUT_2") (pintype "passive"))
      (node (ref "U12") (pin "4") (pinfunction "OUT_4") (pintype "passive"))
      (node (ref "U2") (pin "11") (pinfunction "VDD_11") (pintype "passive"))
      (node (ref "U2") (pin "33") (pinfunction "VDD_33") (pintype "passive"))
      (node (ref "U3") (pin "8") (pinfunction "VCC1_8") (pintype "passive"))
      (node (ref "U4") (pin "3") (pinfunction "WP#_3") (pintype "passive"))
      (node (ref "U4") (pin "7") (pinfunction "HOLD_7") (pintype "passive"))
      (node (ref "U4") (pin "8") (pinfunction "VCC_8") (pintype "passive"))
    )
    (net (code "166") (name "VCC5") (class "Default")
      (node (ref "C45") (pin "2") (pintype "passive"))
      (node (ref "C54") (pin "1") (pintype "passive"))
      (node (ref "C65") (pin "2") (pintype "passive"))
      (node (ref "C66") (pin "2") (pintype "passive"))
      (node (ref "C97") (pin "2") (pintype "passive"))
      (node (ref "L7") (pin "2") (pintype "passive"))
      (node (ref "POWER") (pin "2") (pinfunction "TAP_2") (pintype "passive"))
      (node (ref "R43") (pin "2") (pintype "passive"))
      (node (ref "U12") (pin "3") (pinfunction "IN_3") (pintype "passive"))
      (node (ref "U15") (pin "3") (pinfunction "IN_3") (pintype "passive"))
      (node (ref "U17") (pin "6") (pinfunction "VDD_6") (pintype "passive"))
    )
    (net (code "167") (name "unconnected-(J3-GND-Pad9)") (class "Default")
      (node (ref "J3") (pin "9") (pinfunction "GND_9") (pintype "passive"))
    )
    (net (code "168") (name "unconnected-(J3-GND-Pad10)") (class "Default")
      (node (ref "J3") (pin "10") (pinfunction "GND_10") (pintype "passive"))
    )
    (net (code "169") (name "unconnected-(J3-NC-Pad4)") (class "Default")
      (node (ref "J3") (pin "4") (pinfunction "NC_4") (pintype "passive"))
    )
    (net (code "170") (name "unconnected-(J3-NC-Pad5)") (class "Default")
      (node (ref "J3") (pin "5") (pinfunction "NC_5") (pintype "passive"))
    )
    (net (code "171") (name "unconnected-(POWER-GND-Pad4)") (class "Default")
      (node (ref "POWER") (pin "4") (pinfunction "GND_4") (pintype "passive"))
    )
    (net (code "172") (name "unconnected-(POWER-GND-Pad5)") (class "Default")
      (node (ref "POWER") (pin "5") (pinfunction "GND_5") (pintype "passive"))
    )
    (net (code "173") (name "unconnected-(POWER-I{slash}O-Pad1)") (class "Default")
      (node (ref "POWER") (pin "1") (pinfunction "I/O_1") (pintype "passive"))
    )
    (net (code "174") (name "unconnected-(TFT1-NC-Pad25)") (class "Default")
      (node (ref "TFT1") (pin "25") (pinfunction "NC_25") (pintype "passive"))
    )
    (net (code "175") (name "unconnected-(TFT1-NC-Pad30)") (class "Default")
      (node (ref "TFT1") (pin "30") (pinfunction "NC_30") (pintype "passive"))
    )
    (net (code "176") (name "unconnected-(TFT1-NC-Pad31)") (class "Default")
      (node (ref "TFT1") (pin "31") (pinfunction "NC_31") (pintype "passive"))
    )
    (net (code "177") (name "unconnected-(TFT1-NC-Pad32)") (class "Default")
      (node (ref "TFT1") (pin "32") (pinfunction "NC_32") (pintype "passive"))
    )
    (net (code "178") (name "unconnected-(TFT1-NC-Pad33)") (class "Default")
      (node (ref "TFT1") (pin "33") (pinfunction "NC_33") (pintype "passive"))
    )
    (net (code "179") (name "unconnected-(TFT1-NC-Pad36)") (class "Default")
      (node (ref "TFT1") (pin "36") (pinfunction "NC_36") (pintype "passive"))
    )
    (net (code "180") (name "unconnected-(TFT1-X+-Pad29)") (class "Default")
      (node (ref "TFT1") (pin "29") (pinfunction "X+_29") (pintype "passive"))
    )
    (net (code "181") (name "unconnected-(TFT1-X--Pad27)") (class "Default")
      (node (ref "TFT1") (pin "27") (pinfunction "X-_27") (pintype "passive"))
    )
    (net (code "182") (name "unconnected-(TFT1-Y+-Pad28)") (class "Default")
      (node (ref "TFT1") (pin "28") (pinfunction "Y+_28") (pintype "passive"))
    )
    (net (code "183") (name "unconnected-(TFT1-Y--Pad26)") (class "Default")
      (node (ref "TFT1") (pin "26") (pinfunction "Y-_26") (pintype "passive"))
    )
    (net (code "184") (name "unconnected-(U1-NC-Pad106)") (class "Default")
      (node (ref "U1") (pin "106") (pinfunction "NC_106") (pintype "passive+no_connect"))
    )
    (net (code "185") (name "unconnected-(U19-GPIO2{slash}DCLK-Pad9)") (class "Default")
      (node (ref "U19") (pin "9") (pinfunction "GPIO2/DCLK_9") (pintype "passive+no_connect"))
    )
    (net (code "186") (name "unconnected-(U19-GPIO3{slash}SDATA-Pad10)") (class "Default")
      (node (ref "U19") (pin "10") (pinfunction "GPIO3/SDATA_10") (pintype "passive+no_connect"))
    )
    (net (code "187") (name "unconnected-(U19-GPIO5{slash}I2S_MCLK-Pad25)") (class "Default")
      (node (ref "U19") (pin "25") (pinfunction "GPIO5/I2S_MCLK_25") (pintype "passive+no_connect"))
    )
    (net (code "188") (name "unconnected-(U19-GPIO6{slash}I2S_SCLK-Pad11)") (class "Default")
      (node (ref "U19") (pin "11") (pinfunction "GPIO6/I2S_SCLK_11") (pintype "passive+no_connect"))
    )
    (net (code "189") (name "unconnected-(U19-GPIO7{slash}I2S_SDATA-Pad12)") (class "Default")
      (node (ref "U19") (pin "12") (pinfunction "GPIO7/I2S_SDATA_12") (pintype "passive+no_connect"))
    )
    (net (code "190") (name "unconnected-(U19-TX-Pad27)") (class "Default")
      (node (ref "U19") (pin "27") (pinfunction "TX_27") (pintype "passive+no_connect"))
    )
    (net (code "191") (name "unconnected-(U19-VCO-Pad15)") (class "Default")
      (node (ref "U19") (pin "15") (pinfunction "VCO_15") (pintype "passive+no_connect"))
    )
    (net (code "192") (name "unconnected-(USB_HOST-ID-Pad4)") (class "Default")
      (node (ref "USB_HOST") (pin "4") (pinfunction "ID_4") (pintype "passive"))
    )
  )
)
